# lps_regulator_rev_10.net
KiCad netlist of a schematic drawn in Altium Designer
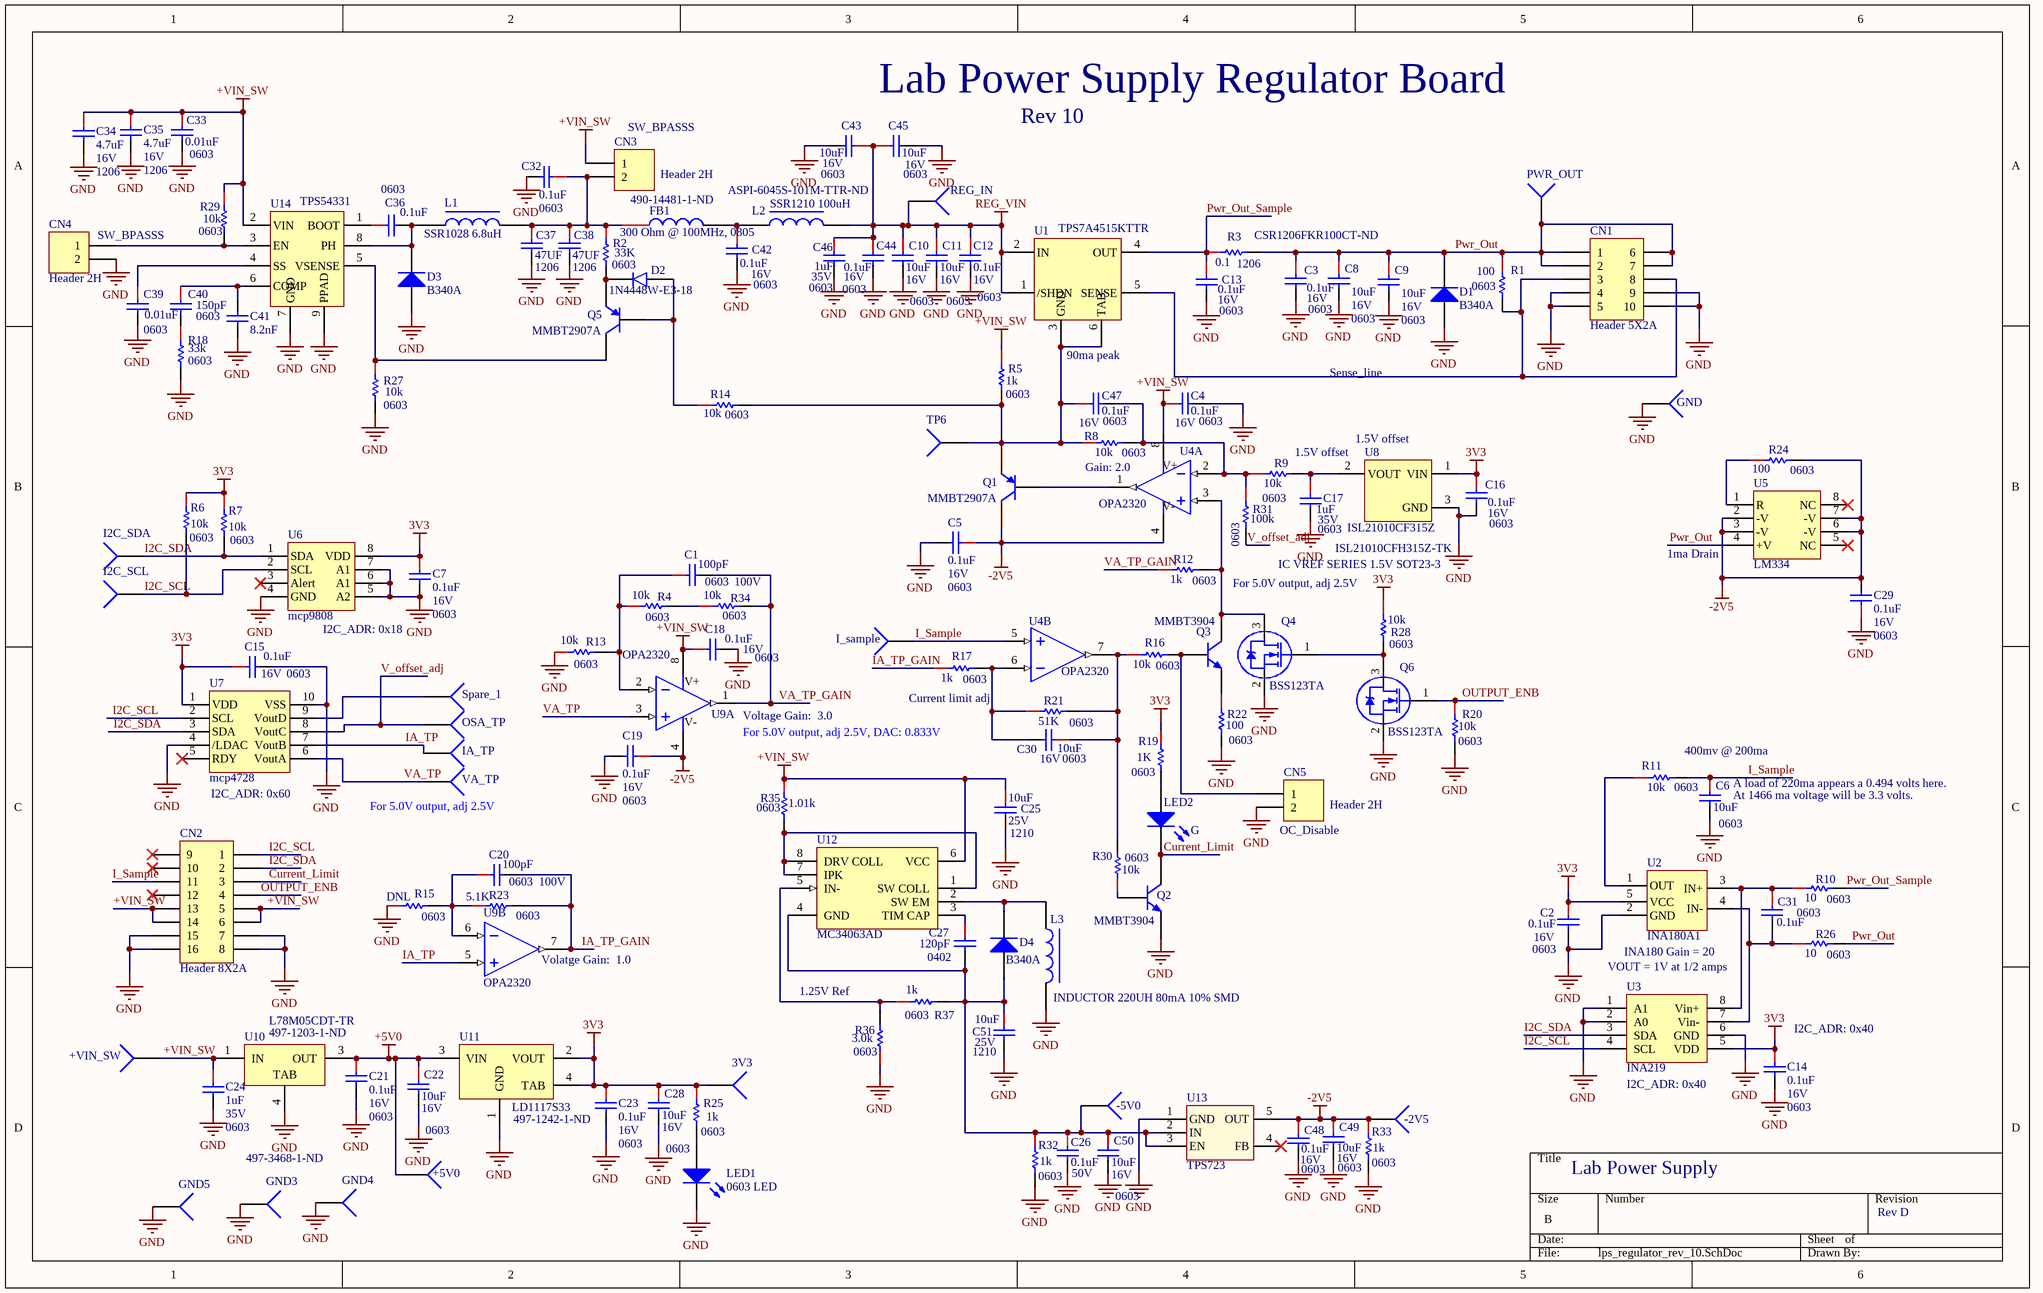
[diagram p0: lps_regulator_rev_10.SchDoc]

(export (version "E")
  (design (tool "Eeschema 10.0.6"))
  (components
    (comp (ref "+5V0")
      (value "TestPoint_BLK")
      (footprint "TestPoint-TH 42 mil")
      (description "Test Point - Black")
      (fields
        (field (name "MANUFACTURER PART NUMBER") "5001")
        (field (name "MANUFACTURER") "Keystone Electronics")
      )
      (libsource (lib "OLogic Nexus Vault") (part "TestPoint_BLK"))
    )
    (comp (ref "+VIN_SW")
      (value "TestPoint_BLK")
      (footprint "TestPoint-TH 42 mil")
      (description "Test Point - Black")
      (fields
        (field (name "MANUFACTURER PART NUMBER") "5001")
        (field (name "MANUFACTURER") "Keystone Electronics")
      )
      (libsource (lib "OLogic Nexus Vault") (part "TestPoint_BLK"))
    )
    (comp (ref "-2V5")
      (value "TestPoint_BLK")
      (footprint "TestPoint-TH 42 mil")
      (description "Test Point - Black")
      (fields
        (field (name "MANUFACTURER PART NUMBER") "5001")
        (field (name "MANUFACTURER") "Keystone Electronics")
      )
      (libsource (lib "OLogic Nexus Vault") (part "TestPoint_BLK"))
    )
    (comp (ref "-5V0")
      (value "TestPoint_BLK")
      (footprint "TestPoint-TH 42 mil")
      (description "Test Point - Black")
      (fields
        (field (name "MANUFACTURER PART NUMBER") "5001")
        (field (name "MANUFACTURER") "Keystone Electronics")
      )
      (libsource (lib "OLogic Nexus Vault") (part "TestPoint_BLK"))
    )
    (comp (ref "3V3")
      (value "TestPoint_BLK")
      (footprint "TestPoint-TH 42 mil")
      (description "Test Point - Black")
      (fields
        (field (name "MANUFACTURER PART NUMBER") "5001")
        (field (name "MANUFACTURER") "Keystone Electronics")
      )
      (libsource (lib "OLogic Nexus Vault") (part "TestPoint_BLK"))
    )
    (comp (ref "C1")
      (value "100pF")
      (footprint "CAPC0603(1608)_N")
      (description "CAP CER 100PF 50V 5% NP0 0603")
      (fields
        (field (name "VOLTAGE (RATED)") "100V")
        (field (name "PACKAGE (IMPERIAL)") "0603")
        (field (name "TOLERANCE") "5%")
      )
      (libsource (lib "OLogic Nexus Vault") (part "=Capacitance"))
    )
    (comp (ref "C2")
      (value "0.1uF")
      (footprint "CAPC0603(1608)_M")
      (description "CAP CER 0.1UF 16V 10% X7R 0603")
      (fields
        (field (name "VOLTAGE (RATED)") "16V")
        (field (name "PACKAGE (IMPERIAL)") "0603")
        (field (name "TOLERANCE") "10%")
      )
      (libsource (lib "OLogic Nexus Vault") (part "=Capacitance"))
    )
    (comp (ref "C3")
      (value "0.1uF")
      (footprint "CAPC0603(1608)_N")
      (description "CAP CER 0.1UF 16V 10% X7R 0603")
      (fields
        (field (name "VOLTAGE (RATED)") "16V")
        (field (name "PACKAGE (IMPERIAL)") "0603")
        (field (name "TOLERANCE") "10%")
      )
      (libsource (lib "OLogic Nexus Vault") (part "=Capacitance"))
    )
    (comp (ref "C4")
      (value "0.1uF")
      (footprint "CAPC0603(1608)_N")
      (description "CAP CER 0.1UF 16V 10% X7R 0603")
      (fields
        (field (name "VOLTAGE (RATED)") "16V")
        (field (name "PACKAGE (IMPERIAL)") "0603")
        (field (name "TOLERANCE") "10%")
      )
      (libsource (lib "OLogic Nexus Vault") (part "=Capacitance"))
    )
    (comp (ref "C5")
      (value "0.1uF")
      (footprint "CAPC0603(1608)_N")
      (description "CAP CER 0.1UF 16V 10% X7R 0603")
      (fields
        (field (name "VOLTAGE (RATED)") "16V")
        (field (name "PACKAGE (IMPERIAL)") "0603")
        (field (name "TOLERANCE") "10%")
      )
      (libsource (lib "OLogic Nexus Vault") (part "=Capacitance"))
    )
    (comp (ref "C6")
      (value "10uF")
      (footprint "CAPC0603(1608)_N")
      (description "CAP CER 10UF 16V X5R 0603")
      (fields (field (name "PACKAGE (IMPERIAL)") "0603") (field (name "TOLERANCE") "10%"))
      (libsource (lib "OLogic Nexus Vault") (part "=Capacitance"))
    )
    (comp (ref "C7")
      (value "0.1uF")
      (footprint "CAPC0603(1608)_M")
      (description "CAP CER 0.1UF 16V 10% X7R 0603")
      (fields
        (field (name "VOLTAGE (RATED)") "16V")
        (field (name "PACKAGE (IMPERIAL)") "0603")
        (field (name "TOLERANCE") "10%")
      )
      (libsource (lib "OLogic Nexus Vault") (part "=Capacitance"))
    )
    (comp (ref "C8")
      (value "10uF")
      (footprint "CAPC0603(1608)_N")
      (description "CAP CER 10UF 16V X5R 0603")
      (fields
        (field (name "VOLTAGE (RATED)") "16V")
        (field (name "PACKAGE (IMPERIAL)") "0603")
        (field (name "TOLERANCE") "10%")
      )
      (libsource (lib "OLogic Nexus Vault") (part "=Capacitance"))
    )
    (comp (ref "C9")
      (value "10uF")
      (footprint "CAPC0603(1608)_N")
      (description "CAP CER 10UF 16V X5R 0603")
      (fields
        (field (name "VOLTAGE (RATED)") "16V")
        (field (name "PACKAGE (IMPERIAL)") "0603")
        (field (name "TOLERANCE") "10%")
      )
      (libsource (lib "OLogic Nexus Vault") (part "=Capacitance"))
    )
    (comp (ref "C10")
      (value "10uF")
      (footprint "CAPC0603(1608)_N")
      (description "CAP CER 10UF 16V X5R 0603")
      (fields
        (field (name "VOLTAGE (RATED)") "16V")
        (field (name "PACKAGE (IMPERIAL)") "0603")
        (field (name "TOLERANCE") "10%")
      )
      (libsource (lib "OLogic Nexus Vault") (part "=Capacitance"))
    )
    (comp (ref "C11")
      (value "10uF")
      (footprint "CAPC0603(1608)_N")
      (description "CAP CER 10UF 16V X5R 0603")
      (fields
        (field (name "VOLTAGE (RATED)") "16V")
        (field (name "PACKAGE (IMPERIAL)") "0603")
        (field (name "TOLERANCE") "10%")
      )
      (libsource (lib "OLogic Nexus Vault") (part "=Capacitance"))
    )
    (comp (ref "C12")
      (value "0.1uF")
      (footprint "CAPC0603(1608)_N")
      (description "CAP CER 0.1UF 16V 10% X7R 0603")
      (fields
        (field (name "VOLTAGE (RATED)") "16V")
        (field (name "PACKAGE (IMPERIAL)") "0603")
        (field (name "TOLERANCE") "10%")
      )
      (libsource (lib "OLogic Nexus Vault") (part "=Capacitance"))
    )
    (comp (ref "C13")
      (value "0.1uF")
      (footprint "CAPC0603(1608)_M")
      (description "CAP CER 0.1UF 16V 10% X7R 0603")
      (fields
        (field (name "VOLTAGE (RATED)") "16V")
        (field (name "PACKAGE (IMPERIAL)") "0603")
        (field (name "TOLERANCE") "10%")
      )
      (libsource (lib "OLogic Nexus Vault") (part "=Capacitance"))
    )
    (comp (ref "C14")
      (value "0.1uF")
      (footprint "CAPC0603(1608)_N")
      (description "CAP CER 0.1UF 16V 10% X7R 0603")
      (fields
        (field (name "VOLTAGE (RATED)") "16V")
        (field (name "PACKAGE (IMPERIAL)") "0603")
        (field (name "TOLERANCE") "10%")
      )
      (libsource (lib "OLogic Nexus Vault") (part "=Capacitance"))
    )
    (comp (ref "C15")
      (value "0.1uF")
      (footprint "CAPC0603(1608)_N")
      (description "CAP CER 0.1UF 16V 10% X7R 0603")
      (fields
        (field (name "VOLTAGE (RATED)") "16V")
        (field (name "PACKAGE (IMPERIAL)") "0603")
        (field (name "TOLERANCE") "10%")
      )
      (libsource (lib "OLogic Nexus Vault") (part "=Capacitance"))
    )
    (comp (ref "C16")
      (value "0.1uF")
      (footprint "CAPC0603(1608)_N")
      (description "CAP CER 0.1UF 16V 10% X7R 0603")
      (fields
        (field (name "VOLTAGE (RATED)") "16V")
        (field (name "PACKAGE (IMPERIAL)") "0603")
        (field (name "TOLERANCE") "10%")
      )
      (libsource (lib "OLogic Nexus Vault") (part "=Capacitance"))
    )
    (comp (ref "C17")
      (value "1uF")
      (footprint "CAPC0603(1608)_M")
      (description "CAP CER 1UF 35V 10% X5R 0603")
      (fields
        (field (name "VOLTAGE (RATED)") "35V")
        (field (name "PACKAGE (IMPERIAL)") "0603")
        (field (name "TOLERANCE") "10%")
      )
      (libsource (lib "OLogic Nexus Vault") (part "=Capacitance"))
    )
    (comp (ref "C18")
      (value "0.1uF")
      (footprint "CAPC0603(1608)_M")
      (description "CAP CER 0.1UF 16V 10% X7R 0603")
      (fields
        (field (name "VOLTAGE (RATED)") "16V")
        (field (name "PACKAGE (IMPERIAL)") "0603")
        (field (name "TOLERANCE") "10%")
      )
      (libsource (lib "OLogic Nexus Vault") (part "=Capacitance"))
    )
    (comp (ref "C19")
      (value "0.1uF")
      (footprint "CAPC0603(1608)_M")
      (description "CAP CER 0.1UF 16V 10% X7R 0603")
      (fields
        (field (name "VOLTAGE (RATED)") "16V")
        (field (name "PACKAGE (IMPERIAL)") "0603")
        (field (name "TOLERANCE") "10%")
      )
      (libsource (lib "OLogic Nexus Vault") (part "=Capacitance"))
    )
    (comp (ref "C20")
      (value "100pF")
      (footprint "CAPC0603(1608)_N")
      (description "CAP CER 100PF 50V 5% NP0 0603")
      (fields
        (field (name "VOLTAGE (RATED)") "100V")
        (field (name "PACKAGE (IMPERIAL)") "0603")
        (field (name "TOLERANCE") "5%")
      )
      (libsource (lib "OLogic Nexus Vault") (part "=Capacitance"))
    )
    (comp (ref "C21")
      (value "0.1uF")
      (footprint "CAPC0603(1608)_M")
      (description "CAP CER 0.1UF 16V 10% X7R 0603")
      (fields
        (field (name "VOLTAGE (RATED)") "16V")
        (field (name "PACKAGE (IMPERIAL)") "0603")
        (field (name "TOLERANCE") "10%")
      )
      (libsource (lib "OLogic Nexus Vault") (part "=Capacitance"))
    )
    (comp (ref "C22")
      (value "10uF")
      (footprint "CAPC0603(1608)_N")
      (description "CAP CER 10UF 16V X5R 0603")
      (fields
        (field (name "VOLTAGE (RATED)") "16V")
        (field (name "PACKAGE (IMPERIAL)") "0603")
        (field (name "TOLERANCE") "10%")
      )
      (libsource (lib "OLogic Nexus Vault") (part "=Capacitance"))
    )
    (comp (ref "C23")
      (value "0.1uF")
      (footprint "CAPC0603(1608)_M")
      (description "CAP CER 0.1UF 16V 10% X7R 0603")
      (fields
        (field (name "VOLTAGE (RATED)") "16V")
        (field (name "PACKAGE (IMPERIAL)") "0603")
        (field (name "TOLERANCE") "10%")
      )
      (libsource (lib "OLogic Nexus Vault") (part "=Capacitance"))
    )
    (comp (ref "C24")
      (value "1uF")
      (footprint "CAPC0603(1608)_M")
      (description "CAP CER 1UF 35V 10% X5R 0603")
      (fields
        (field (name "VOLTAGE (RATED)") "35V")
        (field (name "PACKAGE (IMPERIAL)") "0603")
        (field (name "TOLERANCE") "10%")
      )
      (libsource (lib "OLogic Nexus Vault") (part "=Capacitance"))
    )
    (comp (ref "C25")
      (value "10uF")
      (footprint "CAPC1210(3225)_L")
      (description "CAP CER 10UF 25V JB 1210")
      (fields
        (field (name "VOLTAGE (RATED)") "25V")
        (field (name "PACKAGE (IMPERIAL)") "1210")
        (field (name "TOLERANCE") "10%")
      )
      (libsource (lib "OLogic Nexus Vault") (part "=Capacitance"))
    )
    (comp (ref "C26")
      (value "0.1uF")
      (footprint "CAPC0805(2012)_N")
      (description "0.1uF 0805 50V")
      (fields
        (field (name "MANUFACTURER") "Kemet")
        (field (name "MANUFACTURER PART NUMBER") "C0805C104K5RACTU")
        (field (name "VOLTAGE - RATED") "50V")
      )
      (libsource (lib "OLogic-Passive") (part "CAP CER 0.1UF 50V 10% X7R 0805"))
    )
    (comp (ref "C27")
      (value "120pF")
      (footprint "CAPC0402(1005)_L")
      (description "CAP CER 100PF 50V C0G/NP0 0402")
      (fields (field (name "PACKAGE (IMPERIAL)") "0402") (field (name "TOLERANCE") "1%"))
      (libsource (lib "OLogic Nexus Vault") (part "=Capacitance"))
    )
    (comp (ref "C28")
      (value "10uF")
      (footprint "CAPC0603(1608)_N")
      (description "CAP CER 10UF 16V X5R 0603")
      (fields
        (field (name "VOLTAGE (RATED)") "16V")
        (field (name "PACKAGE (IMPERIAL)") "0603")
        (field (name "TOLERANCE") "10%")
      )
      (libsource (lib "OLogic Nexus Vault") (part "=Capacitance"))
    )
    (comp (ref "C29")
      (value "0.1uF")
      (footprint "CAPC0603(1608)_M")
      (description "CAP CER 0.1UF 16V 10% X7R 0603")
      (fields
        (field (name "VOLTAGE (RATED)") "16V")
        (field (name "PACKAGE (IMPERIAL)") "0603")
        (field (name "TOLERANCE") "10%")
      )
      (libsource (lib "OLogic Nexus Vault") (part "=Capacitance"))
    )
    (comp (ref "C30")
      (value "10uF")
      (footprint "CAPC0603(1608)_M")
      (description "CAP CER 0.1UF 16V 10% X7R 0603")
      (fields
        (field (name "VOLTAGE (RATED)") "16V")
        (field (name "PACKAGE (IMPERIAL)") "0603")
        (field (name "TOLERANCE") "10%")
      )
      (libsource (lib "OLogic Nexus Vault") (part "=Capacitance"))
    )
    (comp (ref "C31")
      (value "0.1uF")
      (footprint "CAPC0603(1608)_N")
      (description "CAP CER 0.1UF 16V 10% X7R 0603")
      (fields (field (name "PACKAGE (IMPERIAL)") "0603") (field (name "TOLERANCE") "10%"))
      (libsource (lib "OLogic Nexus Vault") (part "=Capacitance"))
    )
    (comp (ref "C32")
      (value "0.1uF")
      (footprint "CAPC0603(1608)_N")
      (description "CAP CER 0.1UF 16V 10% X7R 0603")
      (fields (field (name "PACKAGE (IMPERIAL)") "0603") (field (name "TOLERANCE") "10%"))
      (libsource (lib "OLogic Nexus Vault") (part "=Capacitance"))
    )
    (comp (ref "C33")
      (value "0.01uF")
      (footprint "CAPC0603(1608)_N")
      (description "CAP CER 0.01uF 50V 10% X7R 0603")
      (fields (field (name "PACKAGE (IMPERIAL)") "0603") (field (name "TOLERANCE") "10%"))
      (libsource (lib "OLogic Nexus Vault") (part "=Capacitance"))
    )
    (comp (ref "C34")
      (value "4.7uF")
      (footprint "CAPC1206(3216)_N")
      (description "CAP CER 4.7UF 50V 10% X7R 1206")
      (fields
        (field (name "VOLTAGE (RATED)") "16V")
        (field (name "PACKAGE (IMPERIAL)") "1206")
        (field (name "TOLERANCE") "10%")
      )
      (libsource (lib "OLogic Nexus Vault") (part "=Capacitance"))
    )
    (comp (ref "C35")
      (value "4.7uF")
      (footprint "CAPC1206(3216)_N")
      (description "CAP CER 4.7UF 50V 10% X7R 1206")
      (fields
        (field (name "VOLTAGE (RATED)") "16V")
        (field (name "PACKAGE (IMPERIAL)") "1206")
        (field (name "TOLERANCE") "10%")
      )
      (libsource (lib "OLogic Nexus Vault") (part "=Capacitance"))
    )
    (comp (ref "C36")
      (value "0.1uF")
      (footprint "CAPC0603(1608)_N")
      (description "CAP CER 0.1UF 16V 10% X7R 0603")
      (fields (field (name "PACKAGE (IMPERIAL)") "0603") (field (name "TOLERANCE") "10%"))
      (libsource (lib "OLogic Nexus Vault") (part "=Capacitance"))
    )
    (comp (ref "C37")
      (value "47UF")
      (footprint "CAPC1206(3216)_L")
      (description "CAP CER 47UF 25V 1206")
      (fields (field (name "PACKAGE (IMPERIAL)") "1206") (field (name "TOLERANCE") "20%"))
      (libsource (lib "OLogic Nexus Vault") (part "=Capacitance"))
    )
    (comp (ref "C38")
      (value "47UF")
      (footprint "CAPC1206(3216)_L")
      (description "CAP CER 47UF 25V 1206")
      (fields (field (name "PACKAGE (IMPERIAL)") "1206") (field (name "TOLERANCE") "20%"))
      (libsource (lib "OLogic Nexus Vault") (part "=Capacitance"))
    )
    (comp (ref "C39")
      (value "0.01uF")
      (footprint "CAPC0603(1608)_N")
      (description "CAP CER 22PF 50V 5% NP0 0603")
      (fields (field (name "PACKAGE (IMPERIAL)") "0603") (field (name "TOLERANCE") "5%"))
      (libsource (lib "OLogic Nexus Vault") (part "=Capacitance"))
    )
    (comp (ref "C40")
      (value "150pF")
      (footprint "CAPC0603(1608)_M")
      (description "CAP CER 1UF 35V 10% X5R 0603")
      (fields (field (name "PACKAGE (IMPERIAL)") "0603") (field (name "TOLERANCE") "10%"))
      (libsource (lib "OLogic Nexus Vault") (part "=Capacitance"))
    )
    (comp (ref "C41")
      (value "8.2nF")
      (footprint "CAPC1608X87X35ML15T15")
      (description "CAP CER 820PF 50V X7R 0603")
      (fields (field (name "VOLTAGE") "50V") (field (name "TOLERANCE") "10%"))
      (libsource (lib "OLogic Nexus Vault") (part "CAP"))
    )
    (comp (ref "C42")
      (value "0.1uF")
      (footprint "CAPC0603(1608)_N")
      (description "CAP CER 0.1UF 16V 10% X7R 0603")
      (fields
        (field (name "VOLTAGE (RATED)") "16V")
        (field (name "PACKAGE (IMPERIAL)") "0603")
        (field (name "TOLERANCE") "10%")
      )
      (libsource (lib "OLogic Nexus Vault") (part "=Capacitance"))
    )
    (comp (ref "C43")
      (value "10uF")
      (footprint "CAPC0603(1608)_N")
      (description "CAP CER 10UF 16V X5R 0603")
      (fields
        (field (name "VOLTAGE (RATED)") "16V")
        (field (name "PACKAGE (IMPERIAL)") "0603")
        (field (name "TOLERANCE") "10%")
      )
      (libsource (lib "OLogic Nexus Vault") (part "=Capacitance"))
    )
    (comp (ref "C44")
      (value "0.1uF")
      (footprint "CAPC0603(1608)_N")
      (description "CAP CER 0.1UF 16V 10% X7R 0603")
      (fields
        (field (name "VOLTAGE (RATED)") "16V")
        (field (name "PACKAGE (IMPERIAL)") "0603")
        (field (name "TOLERANCE") "10%")
      )
      (libsource (lib "OLogic Nexus Vault") (part "=Capacitance"))
    )
    (comp (ref "C45")
      (value "10uF")
      (footprint "CAPC0603(1608)_N")
      (description "CAP CER 10UF 16V X5R 0603")
      (fields
        (field (name "VOLTAGE (RATED)") "16V")
        (field (name "PACKAGE (IMPERIAL)") "0603")
        (field (name "TOLERANCE") "10%")
      )
      (libsource (lib "OLogic Nexus Vault") (part "=Capacitance"))
    )
    (comp (ref "C46")
      (value "1uF")
      (footprint "CAPC0603(1608)_M")
      (description "CAP CER 1UF 35V 10% X5R 0603")
      (fields
        (field (name "VOLTAGE (RATED)") "35V")
        (field (name "PACKAGE (IMPERIAL)") "0603")
        (field (name "TOLERANCE") "10%")
      )
      (libsource (lib "OLogic Nexus Vault") (part "=Capacitance"))
    )
    (comp (ref "C47")
      (value "0.1uF")
      (footprint "CAPC0603(1608)_N")
      (description "CAP CER 0.1UF 16V 10% X7R 0603")
      (fields
        (field (name "VOLTAGE (RATED)") "16V")
        (field (name "PACKAGE (IMPERIAL)") "0603")
        (field (name "TOLERANCE") "10%")
      )
      (libsource (lib "OLogic Nexus Vault") (part "=Capacitance"))
    )
    (comp (ref "C48")
      (value "0.1uF")
      (footprint "CAPC0603(1608)_M")
      (description "CAP CER 0.1UF 16V 10% X7R 0603")
      (fields
        (field (name "VOLTAGE (RATED)") "16V")
        (field (name "PACKAGE (IMPERIAL)") "0603")
        (field (name "TOLERANCE") "10%")
      )
      (libsource (lib "OLogic Nexus Vault") (part "=Capacitance"))
    )
    (comp (ref "C49")
      (value "10uF")
      (footprint "CAPC0603(1608)_N")
      (description "CAP CER 10UF 16V X5R 0603")
      (fields
        (field (name "VOLTAGE (RATED)") "16V")
        (field (name "PACKAGE (IMPERIAL)") "0603")
        (field (name "TOLERANCE") "10%")
      )
      (libsource (lib "OLogic Nexus Vault") (part "=Capacitance"))
    )
    (comp (ref "C50")
      (value "10uF")
      (footprint "CAPC0603(1608)_N")
      (description "CAP CER 10UF 16V X5R 0603")
      (fields
        (field (name "VOLTAGE (RATED)") "16V")
        (field (name "PACKAGE (IMPERIAL)") "0603")
        (field (name "TOLERANCE") "10%")
      )
      (libsource (lib "OLogic Nexus Vault") (part "=Capacitance"))
    )
    (comp (ref "C51")
      (value "10uF")
      (footprint "CAPC1210(3225)_L")
      (description "CAP CER 10UF 25V JB 1210")
      (fields
        (field (name "VOLTAGE (RATED)") "25V")
        (field (name "PACKAGE (IMPERIAL)") "1210")
        (field (name "TOLERANCE") "10%")
      )
      (libsource (lib "OLogic Nexus Vault") (part "=Capacitance"))
    )
    (comp (ref "CN1")
      (value "Header 5X2A")
      (footprint "HDR2X5_CEN")
      (description "Header, 5-Pin, Dual row")
      (fields (field (name "PUBLISHER") "Altium Limited"))
      (libsource (lib "OLogic Nexus Vault") (part "Header 5X2A"))
    )
    (comp (ref "CN2")
      (value "Header 8X2A")
      (footprint "HDR2X8_CEN")
      (description "Header, 8-Pin, Dual row")
      (fields (field (name "PUBLISHER") "Altium Limited"))
      (libsource (lib "OLogic Nexus Vault") (part "Header 8X2A"))
    )
    (comp (ref "CN3")
      (value "Header 2H")
      (footprint "HDR1X2H")
      (description "Header, 2-Pin, Right Angle")
      (fields
        (field (name "MANUFACTURER PART NUMBER") "M20-9960245")
        (field (name "MANUFACTURER") "Harwin Inc.")
        (field (name "PUBLISHER") "Altium Limited")
      )
      (libsource (lib "OLogic Nexus Vault") (part "Header 2H"))
    )
    (comp (ref "CN4")
      (value "Header 2H")
      (footprint "HDR1X2H")
      (description "Header, 2-Pin, Right Angle")
      (fields
        (field (name "MANUFACTURER PART NUMBER") "M20-9960245")
        (field (name "MANUFACTURER") "Harwin Inc.")
        (field (name "PUBLISHER") "Altium Limited")
      )
      (libsource (lib "") (part "Header 2H_1"))
    )
    (comp (ref "CN5")
      (value "Header 2H")
      (footprint "HDR1X2H")
      (description "Header, 2-Pin, Right Angle")
      (fields
        (field (name "MANUFACTURER PART NUMBER") "M20-9960245")
        (field (name "MANUFACTURER") "Harwin Inc.")
        (field (name "PUBLISHER") "Altium Limited")
      )
      (libsource (lib "OLogic Nexus Vault") (part "Header 2H"))
    )
    (comp (ref "D1")
      (value "B340A")
      (footprint "DO-214AC")
      (description "DIODE SCHOTTKY 60V 3A")
      (fields
        (field (name "MANUFACTURER") "Micro Commercial Co")
        (field (name "MANUFACTURER PART NUMBER") "SK36A-LTP")
      )
      (libsource (lib "OLogic Nexus Vault") (part "SK36A-LTP"))
    )
    (comp (ref "D2")
      (value "1N4448W-E3-18")
      (footprint "SOD123")
      (description "Diodes - General Purpose, Power, Switching 100 Volt 500mA 4ns")
      (libsource (lib "OLogic Nexus Vault") (part "1N4448W-E3-18"))
    )
    (comp (ref "D3")
      (value "B340A")
      (footprint "DO-214AC")
      (description "DIODE SCHOTTKY 60V 3A")
      (fields
        (field (name "MANUFACTURER") "Micro Commercial Co")
        (field (name "MANUFACTURER PART NUMBER") "SK36A-LTP")
      )
      (libsource (lib "OLogic Nexus Vault") (part "SK36A-LTP"))
    )
    (comp (ref "D4")
      (value "B340A")
      (footprint "DO-214AC")
      (description "DIODE SCHOTTKY 60V 3A")
      (fields
        (field (name "MANUFACTURER") "Micro Commercial Co")
        (field (name "MANUFACTURER PART NUMBER") "SK36A-LTP")
      )
      (libsource (lib "OLogic Nexus Vault") (part "SK36A-LTP"))
    )
    (comp (ref "FB1")
      (value "300 Ohm @ 100MHz, 0805")
      (footprint "RESC0805(2012)_N")
      (description "600 Ohms @ 100MHz 1 Signal Line Ferrite Bead 0805 (2012 Metric) 2A 150mOhm")
      (fields
        (field (name "MANUFACTURER PART NUMBER") "742792040")
        (field (name "MANUFACTURER") "Wurth Electronics Inc")
        (field (name "CREATOR") "osman")
      )
      (libsource (lib "OLogic Nexus Vault") (part "OL_Ferrite"))
    )
    (comp (ref "GND")
      (value "TestPoint_BLK")
      (footprint "TestPoint-TH 42 mil")
      (description "Test Point - Black")
      (fields
        (field (name "MANUFACTURER PART NUMBER") "5001")
        (field (name "MANUFACTURER") "Keystone Electronics")
      )
      (libsource (lib "OLogic Nexus Vault") (part "TestPoint_BLK"))
    )
    (comp (ref "GND3")
      (value "TestPoint_BLK")
      (footprint "TestPoint-TH 42 mil")
      (description "Test Point - Black")
      (fields
        (field (name "MANUFACTURER PART NUMBER") "5001")
        (field (name "MANUFACTURER") "Keystone Electronics")
      )
      (libsource (lib "OLogic Nexus Vault") (part "TestPoint_BLK"))
    )
    (comp (ref "GND4")
      (value "TestPoint_BLK")
      (footprint "TestPoint-TH 42 mil")
      (description "Test Point - Black")
      (fields
        (field (name "MANUFACTURER PART NUMBER") "5001")
        (field (name "MANUFACTURER") "Keystone Electronics")
      )
      (libsource (lib "OLogic Nexus Vault") (part "TestPoint_BLK"))
    )
    (comp (ref "GND5")
      (value "TestPoint_BLK")
      (footprint "TestPoint-TH 42 mil")
      (description "Test Point - Black")
      (fields
        (field (name "MANUFACTURER PART NUMBER") "5001")
        (field (name "MANUFACTURER") "Keystone Electronics")
      )
      (libsource (lib "OLogic Nexus Vault") (part "TestPoint_BLK"))
    )
    (comp (ref "I2C_SCL")
      (value "TestPoint_BLK")
      (footprint "TestPoint-TH 42 mil")
      (description "Test Point - Black")
      (fields
        (field (name "MANUFACTURER PART NUMBER") "5001")
        (field (name "MANUFACTURER") "Keystone Electronics")
      )
      (libsource (lib "OLogic Nexus Vault") (part "TestPoint_BLK"))
    )
    (comp (ref "I2C_SDA")
      (value "TestPoint_BLK")
      (footprint "TestPoint-TH 42 mil")
      (description "Test Point - Black")
      (fields
        (field (name "MANUFACTURER PART NUMBER") "5001")
        (field (name "MANUFACTURER") "Keystone Electronics")
      )
      (libsource (lib "OLogic Nexus Vault") (part "TestPoint_BLK"))
    )
    (comp (ref "IA_TP")
      (value "TestPoint_BLK")
      (footprint "TestPoint-TH 42 mil")
      (description "Test Point - Black")
      (fields
        (field (name "MANUFACTURER PART NUMBER") "5001")
        (field (name "MANUFACTURER") "Keystone Electronics")
      )
      (libsource (lib "OLogic Nexus Vault") (part "TestPoint_BLK"))
    )
    (comp (ref "I_sample")
      (value "TestPoint_BLK")
      (footprint "TestPoint-TH 42 mil")
      (description "Test Point - Black")
      (fields
        (field (name "MANUFACTURER PART NUMBER") "5001")
        (field (name "MANUFACTURER") "Keystone Electronics")
      )
      (libsource (lib "OLogic Nexus Vault") (part "TestPoint_BLK"))
    )
    (comp (ref "L1")
      (value "SSR1028 6.8uH")
      (footprint "SRU1028")
      (description "INDUCTOR 6.8uH  SMD")
      (fields (field (name "TOLERANCE") "30%"))
      (libsource (lib "OLogic Nexus Vault") (part "SSR1028"))
    )
    (comp (ref "L2")
      (value "SSR1210 100uH")
      (footprint "SRR1210")
      (description "INDUCTOR 100uH 2.2A SMD")
      (fields (field (name "TOLERANCE") "30%"))
      (libsource (lib "OLogic Nexus Vault") (part "SSR1210"))
    )
    (comp (ref "L3")
      (value "INDUCTOR 220UH 80mA 10% SMD")
      (footprint "IND-3218 Chip")
      (description "220uH 3218")
      (fields
        (field (name "MANUFACTURER") "Taiyo Yuden")
        (field (name "MANUFACTURER PART NUMBER") "LB3218T221K")
      )
      (libsource (lib "OLogic Nexus Vault") (part "INDUCTOR 220UH 80mA 10% SMD"))
    )
    (comp (ref "LED1")
      (value "0603 LED")
      (footprint "SM-LED-0603")
      (description "0603 SMD LED")
      (libsource (lib "OLogic Nexus Vault") (part "LED_SINGLE_GENERIC"))
    )
    (comp (ref "LED2")
      (value "G")
      (footprint "SM-LED-0603")
      (description "0603 SMD LED")
      (libsource (lib "OLogic-Diode-Opto-LED") (part "0603 LED"))
    )
    (comp (ref "OSA_TP")
      (value "TestPoint_BLK")
      (footprint "TestPoint-TH 42 mil")
      (description "Test Point - Black")
      (fields
        (field (name "MANUFACTURER PART NUMBER") "5001")
        (field (name "MANUFACTURER") "Keystone Electronics")
      )
      (libsource (lib "OLogic Nexus Vault") (part "TestPoint_BLK"))
    )
    (comp (ref "PWR_OUT")
      (value "TestPoint_BLK")
      (footprint "TestPoint-TH 42 mil")
      (description "Test Point - Black")
      (fields
        (field (name "MANUFACTURER PART NUMBER") "5001")
        (field (name "MANUFACTURER") "Keystone Electronics")
      )
      (libsource (lib "OLogic Nexus Vault") (part "TestPoint_BLK"))
    )
    (comp (ref "Q1")
      (value "MMBT2907A")
      (footprint "SOT23")
      (description "PNP General Purpose Amplifier")
      (fields (field (name "MANUFACTURER") "Fairchild Semiconductor"))
      (libsource (lib "OLogic Nexus Vault") (part "MMBT2907A"))
    )
    (comp (ref "Q2")
      (value "MMBT3904")
      (footprint "SOT23")
      (description "NPN General Purpose Amplifier")
      (fields (field (name "MANUFACTURER") "ON Semiconductor") (field (name "MPN") "MMBT3904WT1G"))
      (libsource (lib "OLogic-Trans-Drivers") (part "MMBT3904"))
    )
    (comp (ref "Q3")
      (value "MMBT3904")
      (footprint "SOT23")
      (description "NPN General Purpose Amplifier")
      (fields (field (name "MANUFACTURER") "ON Semiconductor") (field (name "MPN") "MMBT3904WT1G"))
      (libsource (lib "OLogic-Trans-Drivers") (part "MMBT3904"))
    )
    (comp (ref "Q4")
      (value "BSS123TA")
      (footprint "SOT23-3L")
      (description "MOSFET N-CH 100V 170MA SOT23-3")
      (fields (field (name "MANUFACTURER") "Diodes Incorporated"))
      (libsource (lib "OLogic Nexus Vault") (part "BSS123TA"))
    )
    (comp (ref "Q5")
      (value "MMBT2907A")
      (footprint "SOT23")
      (description "PNP General Purpose Amplifier")
      (fields (field (name "MANUFACTURER") "Fairchild Semiconductor"))
      (libsource (lib "OLogic Nexus Vault") (part "MMBT2907A"))
    )
    (comp (ref "Q6")
      (value "BSS123TA")
      (footprint "SOT23-3L")
      (description "MOSFET N-CH 100V 170MA SOT23-3")
      (fields (field (name "MANUFACTURER") "Diodes Incorporated"))
      (libsource (lib "OLogic Nexus Vault") (part "BSS123TA"))
    )
    (comp (ref "R1")
      (value "100")
      (footprint "RESC0603(1608)_N")
      (description "RES 100 OHM 1% 1/10W 0603 2017")
      (fields
        (field (name "PACKAGE (IMPERIAL)") "0603")
        (field (name "POWER") "100mW")
        (field (name "TOLERANCE") "1%")
        (field (name "RESISTANCE") "100")
      )
      (libsource (lib "OLogic Nexus Vault") (part "=Resistance"))
    )
    (comp (ref "R2")
      (value "10K")
      (footprint "RESC0603(1608)_M")
      (description "RES 10K OHM 1/10W 1% 0603 SMD")
      (fields
        (field (name "PACKAGE (IMPERIAL)") "0603")
        (field (name "RESISTANCE") "33K")
        (field (name "POWER") "100mW")
        (field (name "TOLERANCE") "1%")
      )
      (libsource (lib "OLogic Nexus Vault") (part "=Resistance"))
    )
    (comp (ref "R3")
      (value "0.33")
      (footprint "RESC1206(3216)_N")
      (description "RES 0.33 OHM 1% 1/4W 1206")
      (fields
        (field (name "PACKAGE (IMPERIAL)") "1206")
        (field (name "RESISTANCE") "0.1")
        (field (name "POWER") "250mW")
        (field (name "TOLERANCE") "1%")
      )
      (libsource (lib "OLogic Nexus Vault") (part "=Resistance"))
    )
    (comp (ref "R4")
      (value "10k")
      (footprint "RESC0603(1608)_L")
      (description "RES 10K OHM 0.1% 1/10W 0603")
      (fields
        (field (name "PACKAGE (IMPERIAL)") "0603")
        (field (name "RESISTANCE") "10k")
        (field (name "TOLERANCE") "0.1%")
        (field (name "POWER") "100mW")
      )
      (libsource (lib "OLogic Nexus Vault") (part "=Resistance"))
    )
    (comp (ref "R5")
      (value "10K")
      (footprint "RESC0603(1608)_M")
      (description "RES 10K OHM 1/10W 1% 0603 SMD")
      (fields
        (field (name "PACKAGE (IMPERIAL)") "0603")
        (field (name "RESISTANCE") "1k")
        (field (name "POWER") "100mW")
        (field (name "TOLERANCE") "1%")
      )
      (libsource (lib "OLogic Nexus Vault") (part "=Resistance"))
    )
    (comp (ref "R6")
      (value "10K")
      (footprint "RESC0603(1608)_M")
      (description "RES 10K OHM 1/10W 1% 0603 SMD")
      (fields
        (field (name "PACKAGE (IMPERIAL)") "0603")
        (field (name "RESISTANCE") "10k")
        (field (name "POWER") "100mW")
        (field (name "TOLERANCE") "1%")
      )
      (libsource (lib "OLogic Nexus Vault") (part "=Resistance"))
    )
    (comp (ref "R7")
      (value "10K")
      (footprint "RESC0603(1608)_M")
      (description "RES 10K OHM 1/10W 1% 0603 SMD")
      (fields
        (field (name "PACKAGE (IMPERIAL)") "0603")
        (field (name "RESISTANCE") "10k")
        (field (name "POWER") "100mW")
        (field (name "TOLERANCE") "1%")
      )
      (libsource (lib "OLogic Nexus Vault") (part "=Resistance"))
    )
    (comp (ref "R8")
      (value "10K")
      (footprint "RESC0603(1608)_M")
      (description "RES 10K OHM 1/10W 1% 0603 SMD")
      (fields
        (field (name "PACKAGE (IMPERIAL)") "0603")
        (field (name "RESISTANCE") "10k")
        (field (name "POWER") "100mW")
        (field (name "TOLERANCE") "1%")
      )
      (libsource (lib "OLogic Nexus Vault") (part "=Resistance"))
    )
    (comp (ref "R9")
      (value "10K")
      (footprint "RESC0603(1608)_M")
      (description "RES 10K OHM 1/10W 1% 0603 SMD")
      (fields
        (field (name "PACKAGE (IMPERIAL)") "0603")
        (field (name "RESISTANCE") "10k")
        (field (name "POWER") "100mW")
        (field (name "TOLERANCE") "1%")
      )
      (libsource (lib "OLogic Nexus Vault") (part "=Resistance"))
    )
    (comp (ref "R10")
      (value "10K")
      (footprint "RESC0603(1608)_M")
      (description "RES 10K OHM 1/10W 1% 0603 SMD")
      (fields
        (field (name "PACKAGE (IMPERIAL)") "0603")
        (field (name "RESISTANCE") "10")
        (field (name "POWER") "100mW")
        (field (name "TOLERANCE") "1%")
      )
      (libsource (lib "OLogic Nexus Vault") (part "=Resistance"))
    )
    (comp (ref "R11")
      (value "10K")
      (footprint "RESC0603(1608)_M")
      (description "RES 10K OHM 1/10W 1% 0603 SMD")
      (fields
        (field (name "PACKAGE (IMPERIAL)") "0603")
        (field (name "RESISTANCE") "10k")
        (field (name "POWER") "100mW")
        (field (name "TOLERANCE") "1%")
      )
      (libsource (lib "OLogic Nexus Vault") (part "=Resistance"))
    )
    (comp (ref "R12")
      (value "1.0K")
      (footprint "RESC0603(1608)_M")
      (description "RES 1K OHM 1% 1/10W 0603")
      (fields
        (field (name "PACKAGE (IMPERIAL)") "0603")
        (field (name "POWER") "100mW")
        (field (name "RESISTANCE") "1k")
        (field (name "TOLERANCE") "1%")
      )
      (libsource (lib "OLogic Nexus Vault") (part "=Resistance"))
    )
    (comp (ref "R13")
      (value "10k")
      (footprint "RESC0603(1608)_L")
      (description "RES 10K OHM 0.1% 1/10W 0603")
      (fields
        (field (name "PACKAGE (IMPERIAL)") "0603")
        (field (name "RESISTANCE") "10k")
        (field (name "TOLERANCE") "0.1%")
        (field (name "POWER") "100mW")
      )
      (libsource (lib "OLogic Nexus Vault") (part "=Resistance"))
    )
    (comp (ref "R14")
      (value "10K")
      (footprint "RESC0603(1608)_M")
      (description "RES 10K OHM 1/10W 1% 0603 SMD")
      (fields
        (field (name "PACKAGE (IMPERIAL)") "0603")
        (field (name "RESISTANCE") "10k")
        (field (name "POWER") "100mW")
        (field (name "TOLERANCE") "1%")
      )
      (libsource (lib "OLogic Nexus Vault") (part "=Resistance"))
    )
    (comp (ref "R15")
      (value "1.0K")
      (footprint "RESC0603(1608)_M")
      (description "RES 1K OHM 1% 1/10W 0603")
      (fields
        (field (name "PACKAGE (IMPERIAL)") "0603")
        (field (name "POWER") "100mW")
        (field (name "RESISTANCE") "DNL")
        (field (name "TOLERANCE") "1%")
      )
      (libsource (lib "OLogic Nexus Vault") (part "=Resistance"))
    )
    (comp (ref "R16")
      (value "1.0K")
      (footprint "RESC0603(1608)_M")
      (description "RES 1K OHM 1% 1/10W 0603")
      (fields
        (field (name "PACKAGE (IMPERIAL)") "0603")
        (field (name "POWER") "100mW")
        (field (name "RESISTANCE") "10k")
        (field (name "TOLERANCE") "1%")
      )
      (libsource (lib "OLogic Nexus Vault") (part "=Resistance"))
    )
    (comp (ref "R17")
      (value "1.0K")
      (footprint "RESC0603(1608)_M")
      (description "RES 1K OHM 1% 1/10W 0603")
      (fields
        (field (name "PACKAGE (IMPERIAL)") "0603")
        (field (name "POWER") "100mW")
        (field (name "RESISTANCE") "1k")
        (field (name "TOLERANCE") "1%")
      )
      (libsource (lib "OLogic Nexus Vault") (part "=Resistance"))
    )
    (comp (ref "R18")
      (value "33K")
      (footprint "RESC0603(1608)_N")
      (description "RES 33K OHM 1/10W 5% 0603 SMD")
      (fields
        (field (name "PACKAGE (IMPERIAL)") "0603")
        (field (name "TOLERANCE") "5%")
        (field (name "POWER") "100mW")
        (field (name "RESISTANCE") "33k")
      )
      (libsource (lib "OLogic Nexus Vault") (part "=Resistance"))
    )
    (comp (ref "R19")
      (value "1.0K")
      (footprint "RESC0603(1608)_M")
      (description "RES 1K OHM 1% 1/10W 0603")
      (fields
        (field (name "PACKAGE (IMPERIAL)") "0603")
        (field (name "POWER") "100mW")
        (field (name "RESISTANCE") "1K")
        (field (name "TOLERANCE") "1%")
      )
      (libsource (lib "OLogic Nexus Vault") (part "=Resistance"))
    )
    (comp (ref "R20")
      (value "10K")
      (footprint "RESC0603(1608)_M")
      (description "RES 10K OHM 1/10W 1% 0603 SMD")
      (fields
        (field (name "PACKAGE (IMPERIAL)") "0603")
        (field (name "RESISTANCE") "10k")
        (field (name "POWER") "100mW")
        (field (name "TOLERANCE") "1%")
      )
      (libsource (lib "OLogic Nexus Vault") (part "=Resistance"))
    )
    (comp (ref "R21")
      (value "100K")
      (footprint "RESC0603(1608)_M")
      (description "RES 100K OHM 1% 1/10W 0603")
      (fields
        (field (name "PACKAGE (IMPERIAL)") "0603")
        (field (name "RESISTANCE") "51K")
        (field (name "POWER") "100mW")
        (field (name "TOLERANCE") "1%")
      )
      (libsource (lib "OLogic Nexus Vault") (part "=Resistance"))
    )
    (comp (ref "R22")
      (value "1.0K")
      (footprint "RESC0603(1608)_M")
      (description "RES 1K OHM 1% 1/10W 0603")
      (fields
        (field (name "PACKAGE (IMPERIAL)") "0603")
        (field (name "POWER") "100mW")
        (field (name "RESISTANCE") "100")
        (field (name "TOLERANCE") "1%")
      )
      (libsource (lib "OLogic Nexus Vault") (part "=Resistance"))
    )
    (comp (ref "R23")
      (value "100")
      (footprint "RESC0603(1608)_N")
      (description "RES 100 OHM 1% 1/10W 0603 2017")
      (fields
        (field (name "PACKAGE (IMPERIAL)") "0603")
        (field (name "POWER") "100mW")
        (field (name "TOLERANCE") "1%")
        (field (name "RESISTANCE") "5.1K")
      )
      (libsource (lib "OLogic Nexus Vault") (part "=Resistance"))
    )
    (comp (ref "R24")
      (value "100")
      (footprint "RESC0603(1608)_N")
      (description "RES 100 OHM 1% 1/10W 0603 2017")
      (fields
        (field (name "PACKAGE (IMPERIAL)") "0603")
        (field (name "POWER") "100mW")
        (field (name "TOLERANCE") "1%")
        (field (name "RESISTANCE") "100")
      )
      (libsource (lib "OLogic Nexus Vault") (part "=Resistance"))
    )
    (comp (ref "R25")
      (value "1.0K")
      (footprint "RESC0603(1608)_M")
      (description "RES 1K OHM 1% 1/10W 0603")
      (fields
        (field (name "PACKAGE (IMPERIAL)") "0603")
        (field (name "POWER") "100mW")
        (field (name "RESISTANCE") "1k")
        (field (name "TOLERANCE") "1%")
      )
      (libsource (lib "OLogic Nexus Vault") (part "=Resistance"))
    )
    (comp (ref "R26")
      (value "10K")
      (footprint "RESC0603(1608)_M")
      (description "RES 10K OHM 1/10W 1% 0603 SMD")
      (fields
        (field (name "PACKAGE (IMPERIAL)") "0603")
        (field (name "RESISTANCE") "10")
        (field (name "POWER") "100mW")
        (field (name "TOLERANCE") "1%")
      )
      (libsource (lib "OLogic Nexus Vault") (part "=Resistance"))
    )
    (comp (ref "R27")
      (value "10K")
      (footprint "RESC0603(1608)_M")
      (description "RES 10K OHM 1/10W 1% 0603 SMD")
      (fields
        (field (name "PACKAGE (IMPERIAL)") "0603")
        (field (name "RESISTANCE") "10k")
        (field (name "POWER") "100mW")
        (field (name "TOLERANCE") "1%")
      )
      (libsource (lib "OLogic Nexus Vault") (part "=Resistance"))
    )
    (comp (ref "R28")
      (value "10K")
      (footprint "RESC0603(1608)_M")
      (description "RES 10K OHM 1/10W 1% 0603 SMD")
      (fields
        (field (name "PACKAGE (IMPERIAL)") "0603")
        (field (name "RESISTANCE") "10k")
        (field (name "POWER") "100mW")
        (field (name "TOLERANCE") "1%")
      )
      (libsource (lib "OLogic Nexus Vault") (part "=Resistance"))
    )
    (comp (ref "R29")
      (value "10K")
      (footprint "RESC0603(1608)_M")
      (description "RES 10K OHM 1/10W 1% 0603 SMD")
      (fields
        (field (name "PACKAGE (IMPERIAL)") "0603")
        (field (name "RESISTANCE") "10k")
        (field (name "POWER") "100mW")
        (field (name "TOLERANCE") "1%")
      )
      (libsource (lib "OLogic Nexus Vault") (part "=Resistance"))
    )
    (comp (ref "R30")
      (value "1.0K")
      (footprint "RESC0603(1608)_M")
      (description "RES 1K OHM 1% 1/10W 0603")
      (fields
        (field (name "PACKAGE (IMPERIAL)") "0603")
        (field (name "POWER") "100mW")
        (field (name "RESISTANCE") "10k")
        (field (name "TOLERANCE") "1%")
      )
      (libsource (lib "OLogic Nexus Vault") (part "=Resistance"))
    )
    (comp (ref "R31")
      (value "1.0K")
      (footprint "RESC0603(1608)_M")
      (description "RES 1K OHM 1% 1/10W 0603")
      (fields
        (field (name "PACKAGE (IMPERIAL)") "0603")
        (field (name "POWER") "100mW")
        (field (name "RESISTANCE") "100k")
        (field (name "TOLERANCE") "1%")
      )
      (libsource (lib "OLogic Nexus Vault") (part "=Resistance"))
    )
    (comp (ref "R32")
      (value "1.0K")
      (footprint "RESC0603(1608)_M")
      (description "RES 1K OHM 1% 1/10W 0603")
      (fields
        (field (name "PACKAGE (IMPERIAL)") "0603")
        (field (name "POWER") "100mW")
        (field (name "RESISTANCE") "1k")
        (field (name "TOLERANCE") "1%")
      )
      (libsource (lib "OLogic Nexus Vault") (part "=Resistance"))
    )
    (comp (ref "R33")
      (value "1.0K")
      (footprint "RESC0603(1608)_M")
      (description "RES 1K OHM 1% 1/10W 0603")
      (fields
        (field (name "PACKAGE (IMPERIAL)") "0603")
        (field (name "POWER") "100mW")
        (field (name "RESISTANCE") "1k")
        (field (name "TOLERANCE") "1%")
      )
      (libsource (lib "OLogic Nexus Vault") (part "=Resistance"))
    )
    (comp (ref "R34")
      (value "10k")
      (footprint "RESC0603(1608)_L")
      (description "RES 10K OHM 0.1% 1/10W 0603")
      (fields
        (field (name "PACKAGE (IMPERIAL)") "0603")
        (field (name "RESISTANCE") "10k")
        (field (name "TOLERANCE") "0.1%")
        (field (name "POWER") "100mW")
      )
      (libsource (lib "OLogic Nexus Vault") (part "=Resistance"))
    )
    (comp (ref "R35")
      (value "1.01k")
      (footprint "RESC0603(1608)_M")
      (description "RES 1.01K OHM 1/10W 1% 0603 SMD")
      (fields
        (field (name "PACKAGE (IMPERIAL)") "0603")
        (field (name "TOLERANCE") "0.1%")
        (field (name "POWER") "100mW")
        (field (name "RESISTANCE") "1.01k")
      )
      (libsource (lib "OLogic Nexus Vault") (part "=Resistance"))
    )
    (comp (ref "R36")
      (value "38.3K")
      (footprint "RESC0603(1608)_L")
      (description "RES 38.3K OHM 1/10W 1% 0603")
      (fields
        (field (name "PACKAGE (IMPERIAL)") "0603")
        (field (name "RESISTANCE") "3.0k")
        (field (name "TOLERANCE") "1%")
        (field (name "POWER") "100mW")
      )
      (libsource (lib "OLogic Nexus Vault") (part "=Resistance"))
    )
    (comp (ref "R37")
      (value "38.3K")
      (footprint "RESC0603(1608)_L")
      (description "RES 38.3K OHM 1/10W 1% 0603")
      (fields
        (field (name "PACKAGE (IMPERIAL)") "0603")
        (field (name "RESISTANCE") "1k")
        (field (name "TOLERANCE") "1%")
        (field (name "POWER") "100mW")
      )
      (libsource (lib "OLogic Nexus Vault") (part "=Resistance"))
    )
    (comp (ref "REG_IN")
      (value "TestPoint_BLK")
      (footprint "TestPoint-TH 42 mil")
      (description "Test Point - Black")
      (fields
        (field (name "MANUFACTURER PART NUMBER") "5001")
        (field (name "MANUFACTURER") "Keystone Electronics")
      )
      (libsource (lib "OLogic Nexus Vault") (part "TestPoint_BLK"))
    )
    (comp (ref "Spare_1")
      (value "TestPoint_BLK")
      (footprint "TestPoint-TH 42 mil")
      (description "Test Point - Black")
      (fields
        (field (name "MANUFACTURER PART NUMBER") "5001")
        (field (name "MANUFACTURER") "Keystone Electronics")
      )
      (libsource (lib "OLogic Nexus Vault") (part "TestPoint_BLK"))
    )
    (comp (ref "TP6")
      (value "TestPoint_BLK")
      (footprint "TestPoint-TH 42 mil")
      (description "Test Point - Black")
      (fields
        (field (name "MANUFACTURER PART NUMBER") "5001")
        (field (name "MANUFACTURER") "Keystone Electronics")
      )
      (libsource (lib "OLogic Nexus Vault") (part "TestPoint_BLK"))
    )
    (comp (ref "U1")
      (value "TPS7A4515KTTR")
      (footprint "TPS7A4515KTTR")
      (description "TPS7A4515KTTR, linear regulator")
      (libsource (lib "hdmi_lvds") (part "TPS7A4515KTTR"))
    )
    (comp (ref "U2")
      (value "INA180A1")
      (footprint "SOT-23-5_MC")
      (libsource (lib "hdmi_lvds") (part "INA180A1"))
    )
    (comp (ref "U3")
      (value "INA219")
      (footprint "INA219")
      (description "Current Monitor IC")
      (libsource (lib "hdmi_lvds") (part "INA219"))
    )
    (comp (ref "U4")
      (value "OPA2320")
      (footprint "SOIC-8_NoPad")
      (description "Dual Single Supply Rail-to-Rail OpAmp")
      (fields
        (field (name "MANUFACTURER PART NUMBER") "OPA2320AIDR")
        (field (name "MANUFACTURER") "Texas Instruments")
        (field (name "BASE PART NUMBER") "OPA2320")
      )
      (libsource (lib "OLogic Nexus Vault") (part "OPA2320"))
    )
    (comp (ref "U5")
      (value "LM334")
      (footprint "LM334")
      (description "LM334, Current source")
      (libsource (lib "hdmi_lvds") (part "LM334"))
    )
    (comp (ref "U6") (value "mcp9808") (footprint "8MSOP") (libsource (lib "hdmi_lvds") (part "mcp9808")))
    (comp (ref "U7")
      (value "mcp4728")
      (footprint "MCP4728")
      (description "MCP4728")
      (libsource (lib "hdmi_lvds") (part "mcp4728"))
    )
    (comp (ref "U8")
      (value "ISL21010CF315Z")
      (footprint "SOT23")
      (libsource (lib "hdmi_lvds") (part "ISL21010CF315Z"))
    )
    (comp (ref "U9")
      (value "OPA2320")
      (footprint "SOIC-8_NoPad")
      (description "Dual Single Supply Rail-to-Rail OpAmp")
      (fields
        (field (name "MANUFACTURER PART NUMBER") "OPA2320AIDR")
        (field (name "MANUFACTURER") "Texas Instruments")
        (field (name "BASE PART NUMBER") "OPA2320")
      )
      (libsource (lib "OLogic Nexus Vault") (part "OPA2320"))
    )
    (comp (ref "U10")
      (value "~")
      (footprint "TO-252_N")
      (libsource (lib "OLogic Nexus Vault") (part "PM-REG-LD29150-SOT3"))
    )
    (comp (ref "U11")
      (value "LD1117S33")
      (footprint "DSO-G3")
      (description "3.3 volt fixed regulator, 800mA")
      (libsource (lib "OLogic Nexus Vault") (part "LD1117S33"))
    )
    (comp (ref "U12")
      (value "MC34063AD")
      (footprint "751-05_M")
      (description "DC-to-DC Converter Control Circuit")
      (fields
        (field (name "MANUFACTURER PART NUMBER") "MC34063ECD-TR")
        (field (name "MANUFACTURER") "Fairchild Semi")
      )
      (libsource (lib "OLogic Nexus Vault") (part "MC34063AD"))
    )
    (comp (ref "U13") (value "TPS723") (footprint "SOt-23-5") (libsource (lib "*") (part "TPS723")))
    (comp (ref "U14")
      (value "TPS54331")
      (footprint "TPS54331")
      (libsource (lib "hdmi_lvds") (part "TPS54331"))
    )
    (comp (ref "VA_TP")
      (value "TestPoint_BLK")
      (footprint "TestPoint-TH 42 mil")
      (description "Test Point - Black")
      (fields
        (field (name "MANUFACTURER PART NUMBER") "5001")
        (field (name "MANUFACTURER") "Keystone Electronics")
      )
      (libsource (lib "OLogic Nexus Vault") (part "TestPoint_BLK"))
    )
  )
  (nets
    (net (code "1") (name "+5V0") (class "Default")
      (node (ref "+5V0") (pin "1") (pinfunction "1_1") (pintype "passive"))
      (node (ref "C21") (pin "1") (pinfunction "1_1") (pintype "passive"))
      (node (ref "C22") (pin "1") (pinfunction "1_1") (pintype "passive"))
      (node (ref "U10") (pin "3") (pinfunction "OUT_3") (pintype "power_in"))
      (node (ref "U11") (pin "3") (pinfunction "VIN_3") (pintype "power_in"))
    )
    (net (code "2") (name "+VIN_SW") (class "Default")
      (node (ref "+VIN_SW") (pin "1") (pinfunction "1_1") (pintype "passive"))
      (node (ref "C18") (pin "1") (pinfunction "1_1") (pintype "passive"))
      (node (ref "C24") (pin "1") (pinfunction "1_1") (pintype "passive"))
      (node (ref "C25") (pin "1") (pinfunction "1_1") (pintype "passive"))
      (node (ref "C33") (pin "1") (pinfunction "1_1") (pintype "passive"))
      (node (ref "C34") (pin "1") (pinfunction "1_1") (pintype "passive"))
      (node (ref "C35") (pin "1") (pinfunction "1_1") (pintype "passive"))
      (node (ref "C4") (pin "1") (pinfunction "1_1") (pintype "passive"))
      (node (ref "CN2") (pin "13") (pinfunction "13_13") (pintype "passive"))
      (node (ref "CN2") (pin "14") (pinfunction "14_14") (pintype "passive"))
      (node (ref "CN2") (pin "5") (pinfunction "5_5") (pintype "passive"))
      (node (ref "CN2") (pin "6") (pinfunction "6_6") (pintype "passive"))
      (node (ref "CN3") (pin "1") (pinfunction "1_1") (pintype "passive"))
      (node (ref "R29") (pin "1") (pinfunction "1_1") (pintype "passive"))
      (node (ref "R35") (pin "1") (pinfunction "1_1") (pintype "passive"))
      (node (ref "R5") (pin "1") (pinfunction "1_1") (pintype "passive"))
      (node (ref "U10") (pin "1") (pinfunction "IN_1") (pintype "power_in"))
      (node (ref "U12") (pin "6") (pinfunction "VCC_6") (pintype "power_in"))
      (node (ref "U14") (pin "2") (pinfunction "VIN_2") (pintype "passive"))
      (node (ref "U4") (pin "8") (pinfunction "V+_8") (pintype "power_in"))
      (node (ref "U9") (pin "8") (pinfunction "V+_8") (pintype "power_in"))
    )
    (net (code "3") (name "-2V5") (class "Default")
      (node (ref "-2V5") (pin "1") (pinfunction "1_1") (pintype "passive"))
      (node (ref "C19") (pin "1") (pinfunction "1_1") (pintype "passive"))
      (node (ref "C29") (pin "2") (pinfunction "2_2") (pintype "passive"))
      (node (ref "C48") (pin "1") (pinfunction "1_1") (pintype "passive"))
      (node (ref "C49") (pin "1") (pinfunction "1_1") (pintype "passive"))
      (node (ref "C5") (pin "1") (pinfunction "1_1") (pintype "passive"))
      (node (ref "Q1") (pin "3") (pinfunction "C_3") (pintype "passive"))
      (node (ref "R24") (pin "2") (pinfunction "2_2") (pintype "passive"))
      (node (ref "R33") (pin "1") (pinfunction "1_1") (pintype "passive"))
      (node (ref "U13") (pin "5") (pinfunction "OUT_5") (pintype "passive"))
      (node (ref "U4") (pin "4") (pinfunction "V-_4") (pintype "power_in"))
      (node (ref "U5") (pin "2") (pinfunction "-V_2") (pintype "passive"))
      (node (ref "U5") (pin "3") (pinfunction "-V_3") (pintype "passive"))
      (node (ref "U5") (pin "6") (pinfunction "-V_6") (pintype "passive"))
      (node (ref "U5") (pin "7") (pinfunction "-V_7") (pintype "passive"))
      (node (ref "U9") (pin "4") (pinfunction "V-_4") (pintype "power_in"))
    )
    (net (code "4") (name "/Current_Limit") (class "Default")
      (node (ref "CN2") (pin "3") (pinfunction "3_3") (pintype "passive"))
      (node (ref "LED2") (pin "2") (pinfunction "2_2") (pintype "passive"))
      (node (ref "Q2") (pin "3") (pinfunction "C_3") (pintype "passive"))
    )
    (net (code "5") (name "/I2C_SCL") (class "Default")
      (node (ref "CN2") (pin "1") (pinfunction "1_1") (pintype "passive"))
      (node (ref "I2C_SCL") (pin "1") (pinfunction "1_1") (pintype "passive"))
      (node (ref "R6") (pin "2") (pinfunction "2_2") (pintype "passive"))
      (node (ref "U3") (pin "4") (pinfunction "SCL_4") (pintype "passive"))
      (node (ref "U6") (pin "2") (pinfunction "SCL_2") (pintype "passive"))
      (node (ref "U7") (pin "2") (pinfunction "SCL_2") (pintype "passive"))
    )
    (net (code "6") (name "/I2C_SDA") (class "Default")
      (node (ref "CN2") (pin "2") (pinfunction "2_2") (pintype "passive"))
      (node (ref "I2C_SDA") (pin "1") (pinfunction "1_1") (pintype "passive"))
      (node (ref "R7") (pin "2") (pinfunction "2_2") (pintype "passive"))
      (node (ref "U3") (pin "3") (pinfunction "SDA_3") (pintype "passive"))
      (node (ref "U6") (pin "1") (pinfunction "SDA_1") (pintype "passive"))
      (node (ref "U7") (pin "3") (pinfunction "SDA_3") (pintype "passive"))
    )
    (net (code "7") (name "/IA_TP") (class "Default")
      (node (ref "IA_TP") (pin "1") (pinfunction "1_1") (pintype "passive"))
      (node (ref "U7") (pin "7") (pinfunction "VoutB_7") (pintype "passive"))
      (node (ref "U9") (pin "5") (pinfunction "INB+_5") (pintype "input"))
    )
    (net (code "8") (name "/IA_TP_GAIN") (class "Default")
      (node (ref "C20") (pin "2") (pinfunction "2_2") (pintype "passive"))
      (node (ref "R17") (pin "1") (pinfunction "1_1") (pintype "passive"))
      (node (ref "R23") (pin "2") (pinfunction "2_2") (pintype "passive"))
      (node (ref "U9") (pin "7") (pinfunction "OUTB_7") (pintype "output"))
    )
    (net (code "9") (name "/I_Sample") (class "Default")
      (node (ref "C6") (pin "1") (pinfunction "1_1") (pintype "passive"))
      (node (ref "CN2") (pin "11") (pinfunction "11_11") (pintype "passive"))
      (node (ref "I_sample") (pin "1") (pinfunction "1_1") (pintype "passive"))
      (node (ref "R11") (pin "2") (pinfunction "2_2") (pintype "passive"))
      (node (ref "U4") (pin "5") (pinfunction "INB+_5") (pintype "input"))
    )
    (net (code "10") (name "/OUTPUT_ENB") (class "Default")
      (node (ref "CN2") (pin "4") (pinfunction "4_4") (pintype "passive"))
      (node (ref "Q6") (pin "1") (pinfunction "G_1") (pintype "passive"))
      (node (ref "R20") (pin "1") (pinfunction "1_1") (pintype "passive"))
    )
    (net (code "11") (name "/Pwr_Out") (class "Default")
      (node (ref "C3") (pin "1") (pinfunction "1_1") (pintype "passive"))
      (node (ref "C8") (pin "1") (pinfunction "1_1") (pintype "passive"))
      (node (ref "C9") (pin "1") (pinfunction "1_1") (pintype "passive"))
      (node (ref "CN1") (pin "1") (pinfunction "1_1") (pintype "passive"))
      (node (ref "CN1") (pin "2") (pinfunction "2_2") (pintype "passive"))
      (node (ref "CN1") (pin "6") (pinfunction "6_6") (pintype "passive"))
      (node (ref "CN1") (pin "7") (pinfunction "7_7") (pintype "passive"))
      (node (ref "D1") (pin "2") (pinfunction "K_2") (pintype "passive"))
      (node (ref "PWR_OUT") (pin "1") (pinfunction "1_1") (pintype "passive"))
      (node (ref "R1") (pin "1") (pinfunction "1_1") (pintype "passive"))
      (node (ref "R26") (pin "2") (pinfunction "2_2") (pintype "passive"))
      (node (ref "R3") (pin "2") (pinfunction "2_2") (pintype "passive"))
      (node (ref "U5") (pin "4") (pinfunction "+V_4") (pintype "passive"))
    )
    (net (code "12") (name "/Pwr_Out_Sample") (class "Default")
      (node (ref "C13") (pin "1") (pinfunction "1_1") (pintype "passive"))
      (node (ref "R10") (pin "2") (pinfunction "2_2") (pintype "passive"))
      (node (ref "R3") (pin "1") (pinfunction "1_1") (pintype "passive"))
      (node (ref "U1") (pin "4") (pinfunction "OUT_4") (pintype "passive"))
    )
    (net (code "13") (name "/VA_TP") (class "Default")
      (node (ref "U7") (pin "6") (pinfunction "VoutA_6") (pintype "passive"))
      (node (ref "U9") (pin "3") (pinfunction "INA+_3") (pintype "input"))
      (node (ref "VA_TP") (pin "1") (pinfunction "1_1") (pintype "passive"))
    )
    (net (code "14") (name "/VA_TP_GAIN") (class "Default")
      (node (ref "C1") (pin "2") (pinfunction "2_2") (pintype "passive"))
      (node (ref "R12") (pin "1") (pinfunction "1_1") (pintype "passive"))
      (node (ref "R34") (pin "2") (pinfunction "2_2") (pintype "passive"))
      (node (ref "U9") (pin "1") (pinfunction "OUTA_1") (pintype "output"))
    )
    (net (code "15") (name "/V_offset_adj") (class "Default")
      (node (ref "OSA_TP") (pin "1") (pinfunction "1_1") (pintype "passive"))
      (node (ref "R31") (pin "2") (pinfunction "2_2") (pintype "passive"))
      (node (ref "U7") (pin "8") (pinfunction "VoutC_8") (pintype "passive"))
    )
    (net (code "16") (name "3V3") (class "Default")
      (node (ref "3V3") (pin "1") (pinfunction "1_1") (pintype "passive"))
      (node (ref "C14") (pin "1") (pinfunction "1_1") (pintype "passive"))
      (node (ref "C15") (pin "1") (pinfunction "1_1") (pintype "passive"))
      (node (ref "C16") (pin "1") (pinfunction "1_1") (pintype "passive"))
      (node (ref "C2") (pin "1") (pinfunction "1_1") (pintype "passive"))
      (node (ref "C23") (pin "1") (pinfunction "1_1") (pintype "passive"))
      (node (ref "C28") (pin "1") (pinfunction "1_1") (pintype "passive"))
      (node (ref "C7") (pin "1") (pinfunction "1_1") (pintype "passive"))
      (node (ref "R19") (pin "1") (pinfunction "1_1") (pintype "passive"))
      (node (ref "R25") (pin "1") (pinfunction "1_1") (pintype "passive"))
      (node (ref "R28") (pin "1") (pinfunction "1_1") (pintype "passive"))
      (node (ref "R6") (pin "1") (pinfunction "1_1") (pintype "passive"))
      (node (ref "R7") (pin "1") (pinfunction "1_1") (pintype "passive"))
      (node (ref "U11") (pin "2") (pinfunction "VOUT_2") (pintype "power_in"))
      (node (ref "U11") (pin "4") (pinfunction "TAB_4") (pintype "power_in"))
      (node (ref "U2") (pin "5") (pinfunction "VCC_5") (pintype "passive"))
      (node (ref "U3") (pin "5") (pinfunction "VDD_5") (pintype "passive"))
      (node (ref "U6") (pin "8") (pinfunction "VDD_8") (pintype "passive"))
      (node (ref "U7") (pin "1") (pinfunction "VDD_1") (pintype "passive"))
      (node (ref "U8") (pin "1") (pinfunction "VIN_1") (pintype "passive"))
    )
    (net (code "17") (name "GND") (class "Default")
      (node (ref "C10") (pin "2") (pinfunction "2_2") (pintype "passive"))
      (node (ref "C11") (pin "2") (pinfunction "2_2") (pintype "passive"))
      (node (ref "C12") (pin "2") (pinfunction "2_2") (pintype "passive"))
      (node (ref "C13") (pin "2") (pinfunction "2_2") (pintype "passive"))
      (node (ref "C14") (pin "2") (pinfunction "2_2") (pintype "passive"))
      (node (ref "C15") (pin "2") (pinfunction "2_2") (pintype "passive"))
      (node (ref "C16") (pin "2") (pinfunction "2_2") (pintype "passive"))
      (node (ref "C17") (pin "2") (pinfunction "2_2") (pintype "passive"))
      (node (ref "C18") (pin "2") (pinfunction "2_2") (pintype "passive"))
      (node (ref "C19") (pin "2") (pinfunction "2_2") (pintype "passive"))
      (node (ref "C2") (pin "2") (pinfunction "2_2") (pintype "passive"))
      (node (ref "C21") (pin "2") (pinfunction "2_2") (pintype "passive"))
      (node (ref "C22") (pin "2") (pinfunction "2_2") (pintype "passive"))
      (node (ref "C23") (pin "2") (pinfunction "2_2") (pintype "passive"))
      (node (ref "C24") (pin "2") (pinfunction "2_2") (pintype "passive"))
      (node (ref "C25") (pin "2") (pinfunction "2_2") (pintype "passive"))
      (node (ref "C26") (pin "2") (pinfunction "2_2") (pintype "passive"))
      (node (ref "C28") (pin "2") (pinfunction "2_2") (pintype "passive"))
      (node (ref "C29") (pin "1") (pinfunction "1_1") (pintype "passive"))
      (node (ref "C3") (pin "2") (pinfunction "2_2") (pintype "passive"))
      (node (ref "C32") (pin "2") (pinfunction "2_2") (pintype "passive"))
      (node (ref "C33") (pin "2") (pinfunction "2_2") (pintype "passive"))
      (node (ref "C34") (pin "2") (pinfunction "2_2") (pintype "passive"))
      (node (ref "C35") (pin "2") (pinfunction "2_2") (pintype "passive"))
      (node (ref "C37") (pin "2") (pinfunction "2_2") (pintype "passive"))
      (node (ref "C38") (pin "2") (pinfunction "2_2") (pintype "passive"))
      (node (ref "C39") (pin "2") (pinfunction "2_2") (pintype "passive"))
      (node (ref "C4") (pin "2") (pinfunction "2_2") (pintype "passive"))
      (node (ref "C41") (pin "1") (pinfunction "1_1") (pintype "passive"))
      (node (ref "C42") (pin "2") (pinfunction "2_2") (pintype "passive"))
      (node (ref "C43") (pin "2") (pinfunction "2_2") (pintype "passive"))
      (node (ref "C44") (pin "2") (pinfunction "2_2") (pintype "passive"))
      (node (ref "C45") (pin "2") (pinfunction "2_2") (pintype "passive"))
      (node (ref "C46") (pin "2") (pinfunction "2_2") (pintype "passive"))
      (node (ref "C48") (pin "2") (pinfunction "2_2") (pintype "passive"))
      (node (ref "C49") (pin "2") (pinfunction "2_2") (pintype "passive"))
      (node (ref "C5") (pin "2") (pinfunction "2_2") (pintype "passive"))
      (node (ref "C50") (pin "2") (pinfunction "2_2") (pintype "passive"))
      (node (ref "C51") (pin "2") (pinfunction "2_2") (pintype "passive"))
      (node (ref "C6") (pin "2") (pinfunction "2_2") (pintype "passive"))
      (node (ref "C7") (pin "2") (pinfunction "2_2") (pintype "passive"))
      (node (ref "C8") (pin "2") (pinfunction "2_2") (pintype "passive"))
      (node (ref "C9") (pin "2") (pinfunction "2_2") (pintype "passive"))
      (node (ref "CN1") (pin "10") (pinfunction "10_10") (pintype "passive"))
      (node (ref "CN1") (pin "4") (pinfunction "4_4") (pintype "passive"))
      (node (ref "CN1") (pin "5") (pinfunction "5_5") (pintype "passive"))
      (node (ref "CN1") (pin "9") (pinfunction "9_9") (pintype "passive"))
      (node (ref "CN2") (pin "15") (pinfunction "15_15") (pintype "passive"))
      (node (ref "CN2") (pin "16") (pinfunction "16_16") (pintype "passive"))
      (node (ref "CN2") (pin "7") (pinfunction "7_7") (pintype "passive"))
      (node (ref "CN2") (pin "8") (pinfunction "8_8") (pintype "passive"))
      (node (ref "CN4") (pin "2") (pinfunction "2_2") (pintype "passive"))
      (node (ref "CN5") (pin "2") (pinfunction "2_2") (pintype "passive"))
      (node (ref "D1") (pin "1") (pinfunction "A_1") (pintype "passive"))
      (node (ref "D3") (pin "1") (pinfunction "A_1") (pintype "passive"))
      (node (ref "GND") (pin "1") (pinfunction "1_1") (pintype "passive"))
      (node (ref "GND3") (pin "1") (pinfunction "1_1") (pintype "passive"))
      (node (ref "GND4") (pin "1") (pinfunction "1_1") (pintype "passive"))
      (node (ref "GND5") (pin "1") (pinfunction "1_1") (pintype "passive"))
      (node (ref "L3") (pin "2") (pinfunction "2_2") (pintype "passive"))
      (node (ref "LED1") (pin "2") (pinfunction "Cathode_2") (pintype "passive"))
      (node (ref "Q2") (pin "2") (pinfunction "E_2") (pintype "passive"))
      (node (ref "Q4") (pin "2") (pinfunction "S_2") (pintype "passive"))
      (node (ref "Q6") (pin "2") (pinfunction "S_2") (pintype "passive"))
      (node (ref "R13") (pin "1") (pinfunction "1_1") (pintype "passive"))
      (node (ref "R15") (pin "1") (pinfunction "1_1") (pintype "passive"))
      (node (ref "R18") (pin "2") (pinfunction "2_2") (pintype "passive"))
      (node (ref "R20") (pin "2") (pinfunction "2_2") (pintype "passive"))
      (node (ref "R22") (pin "2") (pinfunction "2_2") (pintype "passive"))
      (node (ref "R27") (pin "2") (pinfunction "2_2") (pintype "passive"))
      (node (ref "R32") (pin "2") (pinfunction "2_2") (pintype "passive"))
      (node (ref "R33") (pin "2") (pinfunction "2_2") (pintype "passive"))
      (node (ref "R36") (pin "1") (pinfunction "1_1") (pintype "passive"))
      (node (ref "U10") (pin "4") (pinfunction "TAB_4") (pintype "passive"))
      (node (ref "U11") (pin "1") (pinfunction "GND_1") (pintype "power_in"))
      (node (ref "U13") (pin "1") (pinfunction "GND_1") (pintype "passive"))
      (node (ref "U14") (pin "7") (pinfunction "GND_7") (pintype "passive"))
      (node (ref "U14") (pin "9") (pinfunction "PPAD_9") (pintype "passive"))
      (node (ref "U2") (pin "2") (pinfunction "GND_2") (pintype "passive"))
      (node (ref "U3") (pin "1") (pinfunction "A1_1") (pintype "passive"))
      (node (ref "U3") (pin "2") (pinfunction "A0_2") (pintype "passive"))
      (node (ref "U3") (pin "6") (pinfunction "GND_6") (pintype "passive"))
      (node (ref "U6") (pin "4") (pinfunction "GND_4") (pintype "passive"))
      (node (ref "U6") (pin "5") (pinfunction "A2_5") (pintype "passive"))
      (node (ref "U6") (pin "6") (pinfunction "A1_6") (pintype "passive"))
      (node (ref "U6") (pin "7") (pinfunction "A1_7") (pintype "passive"))
      (node (ref "U7") (pin "10") (pinfunction "VSS_10") (pintype "passive"))
      (node (ref "U7") (pin "4") (pinfunction "/LDAC_4") (pintype "passive"))
      (node (ref "U8") (pin "3") (pinfunction "GND_3") (pintype "passive"))
    )
    (net (code "18") (name "Net-(C32-Pad1)") (class "Default")
      (node (ref "C32") (pin "1") (pinfunction "1_1") (pintype "passive"))
      (node (ref "C37") (pin "1") (pinfunction "1_1") (pintype "passive"))
      (node (ref "C38") (pin "1") (pinfunction "1_1") (pintype "passive"))
      (node (ref "CN3") (pin "2") (pinfunction "2_2") (pintype "passive"))
      (node (ref "FB1") (pin "1") (pinfunction "1_1") (pintype "passive"))
      (node (ref "L1") (pin "2") (pinfunction "2_2") (pintype "passive"))
      (node (ref "R2") (pin "1") (pinfunction "1_1") (pintype "passive"))
    )
    (net (code "19") (name "Net-(C40-Pad2)") (class "Default")
      (node (ref "C40") (pin "2") (pinfunction "2_2") (pintype "passive"))
      (node (ref "R18") (pin "1") (pinfunction "1_1") (pintype "passive"))
    )
    (net (code "20") (name "Net-(C42-Pad1)") (class "Default")
      (node (ref "C42") (pin "1") (pinfunction "1_1") (pintype "passive"))
      (node (ref "FB1") (pin "2") (pinfunction "2_2") (pintype "passive"))
      (node (ref "L2") (pin "1") (pinfunction "1_1") (pintype "passive"))
    )
    (net (code "21") (name "Net-(D2-A)") (class "Default")
      (node (ref "D2") (pin "1") (pinfunction "A_1") (pintype "passive"))
      (node (ref "Q5") (pin "1") (pinfunction "B_1") (pintype "passive"))
      (node (ref "R14") (pin "1") (pinfunction "1_1") (pintype "passive"))
    )
    (net (code "22") (name "Net-(D2-C)") (class "Default")
      (node (ref "D2") (pin "2") (pinfunction "C_2") (pintype "passive"))
      (node (ref "Q5") (pin "2") (pinfunction "E_2") (pintype "passive"))
      (node (ref "R2") (pin "2") (pinfunction "2_2") (pintype "passive"))
    )
    (net (code "23") (name "Net-(D3-K)") (class "Default")
      (node (ref "C36") (pin "2") (pinfunction "2_2") (pintype "passive"))
      (node (ref "D3") (pin "2") (pinfunction "K_2") (pintype "passive"))
      (node (ref "L1") (pin "1") (pinfunction "1_1") (pintype "passive"))
      (node (ref "U14") (pin "8") (pinfunction "PH_8") (pintype "passive"))
    )
    (net (code "24") (name "Net-(D4-A)") (class "Default")
      (node (ref "-5V0") (pin "1") (pinfunction "1_1") (pintype "passive"))
      (node (ref "C26") (pin "1") (pinfunction "1_1") (pintype "passive"))
      (node (ref "C27") (pin "2") (pinfunction "2_2") (pintype "passive"))
      (node (ref "C50") (pin "1") (pinfunction "1_1") (pintype "passive"))
      (node (ref "C51") (pin "1") (pinfunction "1_1") (pintype "passive"))
      (node (ref "D4") (pin "1") (pinfunction "A_1") (pintype "passive"))
      (node (ref "R32") (pin "1") (pinfunction "1_1") (pintype "passive"))
      (node (ref "R37") (pin "2") (pinfunction "2_2") (pintype "passive"))
      (node (ref "U12") (pin "4") (pinfunction "GND_4") (pintype "power_in"))
      (node (ref "U13") (pin "2") (pinfunction "IN_2") (pintype "passive"))
      (node (ref "U13") (pin "3") (pinfunction "EN_3") (pintype "passive"))
    )
    (net (code "25") (name "Net-(D4-K)") (class "Default")
      (node (ref "D4") (pin "2") (pinfunction "K_2") (pintype "passive"))
      (node (ref "L3") (pin "1") (pinfunction "1_1") (pintype "passive"))
      (node (ref "U12") (pin "2") (pinfunction "SW_EM_2") (pintype "passive"))
    )
    (net (code "26") (name "Net-(LED1-Anode)") (class "Default")
      (node (ref "LED1") (pin "1") (pinfunction "Anode_1") (pintype "passive"))
      (node (ref "R25") (pin "2") (pinfunction "2_2") (pintype "passive"))
    )
    (net (code "27") (name "Net-(LED2-Pad1)") (class "Default")
      (node (ref "LED2") (pin "1") (pinfunction "1_1") (pintype "passive"))
      (node (ref "R19") (pin "2") (pinfunction "2_2") (pintype "passive"))
    )
    (net (code "28") (name "Net-(Q1-B)") (class "Default")
      (node (ref "Q1") (pin "1") (pinfunction "B_1") (pintype "passive"))
      (node (ref "U4") (pin "1") (pinfunction "OUTA_1") (pintype "output"))
    )
    (net (code "29") (name "Net-(Q1-E)") (class "Default")
      (node (ref "C47") (pin "1") (pinfunction "1_1") (pintype "passive"))
      (node (ref "Q1") (pin "2") (pinfunction "E_2") (pintype "passive"))
      (node (ref "R14") (pin "2") (pinfunction "2_2") (pintype "passive"))
      (node (ref "R5") (pin "2") (pinfunction "2_2") (pintype "passive"))
      (node (ref "R8") (pin "1") (pinfunction "1_1") (pintype "passive"))
      (node (ref "TP6") (pin "1") (pinfunction "1_1") (pintype "passive"))
      (node (ref "U1") (pin "3") (pinfunction "GND_3") (pintype "passive"))
      (node (ref "U1") (pin "6") (pinfunction "TAB_6") (pintype "passive"))
    )
    (net (code "30") (name "Net-(Q2-B)") (class "Default")
      (node (ref "Q2") (pin "1") (pinfunction "B_1") (pintype "passive"))
      (node (ref "R30") (pin "1") (pinfunction "1_1") (pintype "passive"))
    )
    (net (code "31") (name "Net-(Q3-B)") (class "Default")
      (node (ref "CN5") (pin "1") (pinfunction "1_1") (pintype "passive"))
      (node (ref "Q3") (pin "1") (pinfunction "B_1") (pintype "passive"))
      (node (ref "R16") (pin "2") (pinfunction "2_2") (pintype "passive"))
    )
    (net (code "32") (name "Net-(Q3-C)") (class "Default")
      (node (ref "Q3") (pin "3") (pinfunction "C_3") (pintype "passive"))
      (node (ref "Q4") (pin "3") (pinfunction "D_3") (pintype "passive"))
      (node (ref "R12") (pin "2") (pinfunction "2_2") (pintype "passive"))
      (node (ref "U4") (pin "3") (pinfunction "INA+_3") (pintype "input"))
    )
    (net (code "33") (name "Net-(Q3-E)") (class "Default")
      (node (ref "Q3") (pin "2") (pinfunction "E_2") (pintype "passive"))
      (node (ref "R22") (pin "1") (pinfunction "1_1") (pintype "passive"))
    )
    (net (code "34") (name "Net-(Q4-G)") (class "Default")
      (node (ref "Q4") (pin "1") (pinfunction "G_1") (pintype "passive"))
      (node (ref "Q6") (pin "3") (pinfunction "D_3") (pintype "passive"))
      (node (ref "R28") (pin "2") (pinfunction "2_2") (pintype "passive"))
    )
    (net (code "35") (name "Net-(Q5-C)") (class "Default")
      (node (ref "Q5") (pin "3") (pinfunction "C_3") (pintype "passive"))
      (node (ref "R27") (pin "1") (pinfunction "1_1") (pintype "passive"))
      (node (ref "U14") (pin "5") (pinfunction "VSENSE_5") (pintype "passive"))
    )
    (net (code "36") (name "Net-(R34-Pad1)") (class "Default")
      (node (ref "R34") (pin "1") (pinfunction "1_1") (pintype "passive"))
      (node (ref "R4") (pin "2") (pinfunction "2_2") (pintype "passive"))
    )
    (net (code "37") (name "Net-(U1-SENSE)") (class "Default")
      (node (ref "CN1") (pin "3") (pinfunction "3_3") (pintype "passive"))
      (node (ref "CN1") (pin "8") (pinfunction "8_8") (pintype "passive"))
      (node (ref "R1") (pin "2") (pinfunction "2_2") (pintype "passive"))
      (node (ref "U1") (pin "5") (pinfunction "SENSE_5") (pintype "passive"))
    )
    (net (code "38") (name "Net-(U2-IN+)") (class "Default")
      (node (ref "C31") (pin "1") (pinfunction "1_1") (pintype "passive"))
      (node (ref "R10") (pin "1") (pinfunction "1_1") (pintype "passive"))
      (node (ref "U2") (pin "3") (pinfunction "IN+_3") (pintype "passive"))
      (node (ref "U3") (pin "8") (pinfunction "Vin+_8") (pintype "passive"))
    )
    (net (code "39") (name "Net-(U2-IN-)") (class "Default")
      (node (ref "C31") (pin "2") (pinfunction "2_2") (pintype "passive"))
      (node (ref "R26") (pin "1") (pinfunction "1_1") (pintype "passive"))
      (node (ref "U2") (pin "4") (pinfunction "IN-_4") (pintype "passive"))
      (node (ref "U3") (pin "7") (pinfunction "Vin-_7") (pintype "passive"))
    )
    (net (code "40") (name "Net-(U2-OUT)") (class "Default")
      (node (ref "R11") (pin "1") (pinfunction "1_1") (pintype "passive"))
      (node (ref "U2") (pin "1") (pinfunction "OUT_1") (pintype "passive"))
    )
    (net (code "41") (name "Net-(U4A-INA-)") (class "Default")
      (node (ref "C47") (pin "2") (pinfunction "2_2") (pintype "passive"))
      (node (ref "R31") (pin "1") (pinfunction "1_1") (pintype "passive"))
      (node (ref "R8") (pin "2") (pinfunction "2_2") (pintype "passive"))
      (node (ref "R9") (pin "1") (pinfunction "1_1") (pintype "passive"))
      (node (ref "U4") (pin "2") (pinfunction "INA-_2") (pintype "input"))
    )
    (net (code "42") (name "Net-(U4B-INB-)") (class "Default")
      (node (ref "C30") (pin "2") (pinfunction "2_2") (pintype "passive"))
      (node (ref "R17") (pin "2") (pinfunction "2_2") (pintype "passive"))
      (node (ref "R21") (pin "1") (pinfunction "1_1") (pintype "passive"))
      (node (ref "U4") (pin "6") (pinfunction "INB-_6") (pintype "input"))
    )
    (net (code "43") (name "Net-(U4B-OUTB)") (class "Default")
      (node (ref "C30") (pin "1") (pinfunction "1_1") (pintype "passive"))
      (node (ref "R16") (pin "1") (pinfunction "1_1") (pintype "passive"))
      (node (ref "R21") (pin "2") (pinfunction "2_2") (pintype "passive"))
      (node (ref "R30") (pin "2") (pinfunction "2_2") (pintype "passive"))
      (node (ref "U4") (pin "7") (pinfunction "OUTB_7") (pintype "output"))
    )
    (net (code "44") (name "Net-(U5-R)") (class "Default")
      (node (ref "R24") (pin "1") (pinfunction "1_1") (pintype "passive"))
      (node (ref "U5") (pin "1") (pinfunction "R_1") (pintype "passive"))
    )
    (net (code "45") (name "Net-(U7-VoutD)") (class "Default")
      (node (ref "Spare_1") (pin "1") (pinfunction "1_1") (pintype "passive"))
      (node (ref "U7") (pin "9") (pinfunction "VoutD_9") (pintype "passive"))
    )
    (net (code "46") (name "Net-(U8-VOUT)") (class "Default")
      (node (ref "C17") (pin "1") (pinfunction "1_1") (pintype "passive"))
      (node (ref "R9") (pin "2") (pinfunction "2_2") (pintype "passive"))
      (node (ref "U8") (pin "2") (pinfunction "VOUT_2") (pintype "passive"))
    )
    (net (code "47") (name "Net-(U9A-INA-)") (class "Default")
      (node (ref "C1") (pin "1") (pinfunction "1_1") (pintype "passive"))
      (node (ref "R13") (pin "2") (pinfunction "2_2") (pintype "passive"))
      (node (ref "R4") (pin "1") (pinfunction "1_1") (pintype "passive"))
      (node (ref "U9") (pin "2") (pinfunction "INA-_2") (pintype "input"))
    )
    (net (code "48") (name "Net-(U9B-INB-)") (class "Default")
      (node (ref "C20") (pin "1") (pinfunction "1_1") (pintype "passive"))
      (node (ref "R15") (pin "2") (pinfunction "2_2") (pintype "passive"))
      (node (ref "R23") (pin "1") (pinfunction "1_1") (pintype "passive"))
      (node (ref "U9") (pin "6") (pinfunction "INB-_6") (pintype "input"))
    )
    (net (code "49") (name "Net-(U12-DRV_COLL)") (class "Default")
      (node (ref "R35") (pin "2") (pinfunction "2_2") (pintype "passive"))
      (node (ref "U12") (pin "1") (pinfunction "SW_COLL_1") (pintype "passive"))
      (node (ref "U12") (pin "7") (pinfunction "IPK_7") (pintype "passive"))
      (node (ref "U12") (pin "8") (pinfunction "DRV_COLL_8") (pintype "open_collector"))
    )
    (net (code "50") (name "Net-(U12-IN-)") (class "Default")
      (node (ref "R36") (pin "2") (pinfunction "2_2") (pintype "passive"))
      (node (ref "R37") (pin "1") (pinfunction "1_1") (pintype "passive"))
      (node (ref "U12") (pin "5") (pinfunction "IN-_5") (pintype "input"))
    )
    (net (code "51") (name "Net-(U12-TIM_CAP)") (class "Default")
      (node (ref "C27") (pin "1") (pinfunction "1_1") (pintype "passive"))
      (node (ref "U12") (pin "3") (pinfunction "TIM_CAP_3") (pintype "passive"))
    )
    (net (code "52") (name "Net-(U14-BOOT)") (class "Default")
      (node (ref "C36") (pin "1") (pinfunction "1_1") (pintype "passive"))
      (node (ref "U14") (pin "1") (pinfunction "BOOT_1") (pintype "passive"))
    )
    (net (code "53") (name "Net-(U14-COMP)") (class "Default")
      (node (ref "C40") (pin "1") (pinfunction "1_1") (pintype "passive"))
      (node (ref "C41") (pin "2") (pinfunction "2_2") (pintype "passive"))
      (node (ref "U14") (pin "6") (pinfunction "COMP_6") (pintype "passive"))
    )
    (net (code "54") (name "Net-(U14-EN)") (class "Default")
      (node (ref "CN4") (pin "1") (pinfunction "1_1") (pintype "passive"))
      (node (ref "R29") (pin "2") (pinfunction "2_2") (pintype "passive"))
      (node (ref "U14") (pin "3") (pinfunction "EN_3") (pintype "passive"))
    )
    (net (code "55") (name "Net-(U14-SS)") (class "Default")
      (node (ref "C39") (pin "1") (pinfunction "1_1") (pintype "passive"))
      (node (ref "U14") (pin "4") (pinfunction "SS_4") (pintype "passive"))
    )
    (net (code "56") (name "REG_VIN") (class "Default")
      (node (ref "C10") (pin "1") (pinfunction "1_1") (pintype "passive"))
      (node (ref "C11") (pin "1") (pinfunction "1_1") (pintype "passive"))
      (node (ref "C12") (pin "1") (pinfunction "1_1") (pintype "passive"))
      (node (ref "C43") (pin "1") (pinfunction "1_1") (pintype "passive"))
      (node (ref "C44") (pin "1") (pinfunction "1_1") (pintype "passive"))
      (node (ref "C45") (pin "1") (pinfunction "1_1") (pintype "passive"))
      (node (ref "C46") (pin "1") (pinfunction "1_1") (pintype "passive"))
      (node (ref "L2") (pin "2") (pinfunction "2_2") (pintype "passive"))
      (node (ref "REG_IN") (pin "1") (pinfunction "1_1") (pintype "passive"))
      (node (ref "U1") (pin "1") (pinfunction "/SHDN_1") (pintype "passive"))
      (node (ref "U1") (pin "2") (pinfunction "IN_2") (pintype "passive"))
    )
    (net (code "57") (name "unconnected-(CN2-Pad9)") (class "Default")
      (node (ref "CN2") (pin "9") (pinfunction "9_9") (pintype "passive+no_connect"))
    )
    (net (code "58") (name "unconnected-(CN2-Pad10)") (class "Default")
      (node (ref "CN2") (pin "10") (pinfunction "10_10") (pintype "passive+no_connect"))
    )
    (net (code "59") (name "unconnected-(CN2-Pad12)") (class "Default")
      (node (ref "CN2") (pin "12") (pinfunction "12_12") (pintype "passive+no_connect"))
    )
    (net (code "60") (name "unconnected-(U5-NC-Pad5)") (class "Default")
      (node (ref "U5") (pin "5") (pinfunction "NC_5") (pintype "passive+no_connect"))
    )
    (net (code "61") (name "unconnected-(U5-NC-Pad8)") (class "Default")
      (node (ref "U5") (pin "8") (pinfunction "NC_8") (pintype "passive+no_connect"))
    )
    (net (code "62") (name "unconnected-(U6-Alert-Pad3)") (class "Default")
      (node (ref "U6") (pin "3") (pinfunction "Alert_3") (pintype "passive+no_connect"))
    )
    (net (code "63") (name "unconnected-(U7-RDY-Pad5)") (class "Default")
      (node (ref "U7") (pin "5") (pinfunction "RDY_5") (pintype "passive+no_connect"))
    )
    (net (code "64") (name "unconnected-(U13-FB-Pad4)") (class "Default")
      (node (ref "U13") (pin "4") (pinfunction "FB_4") (pintype "passive+no_connect"))
    )
  )
)
